# 2019_FDP_SCHEMA.net
KiCad netlist of a schematic drawn in Altium Designer
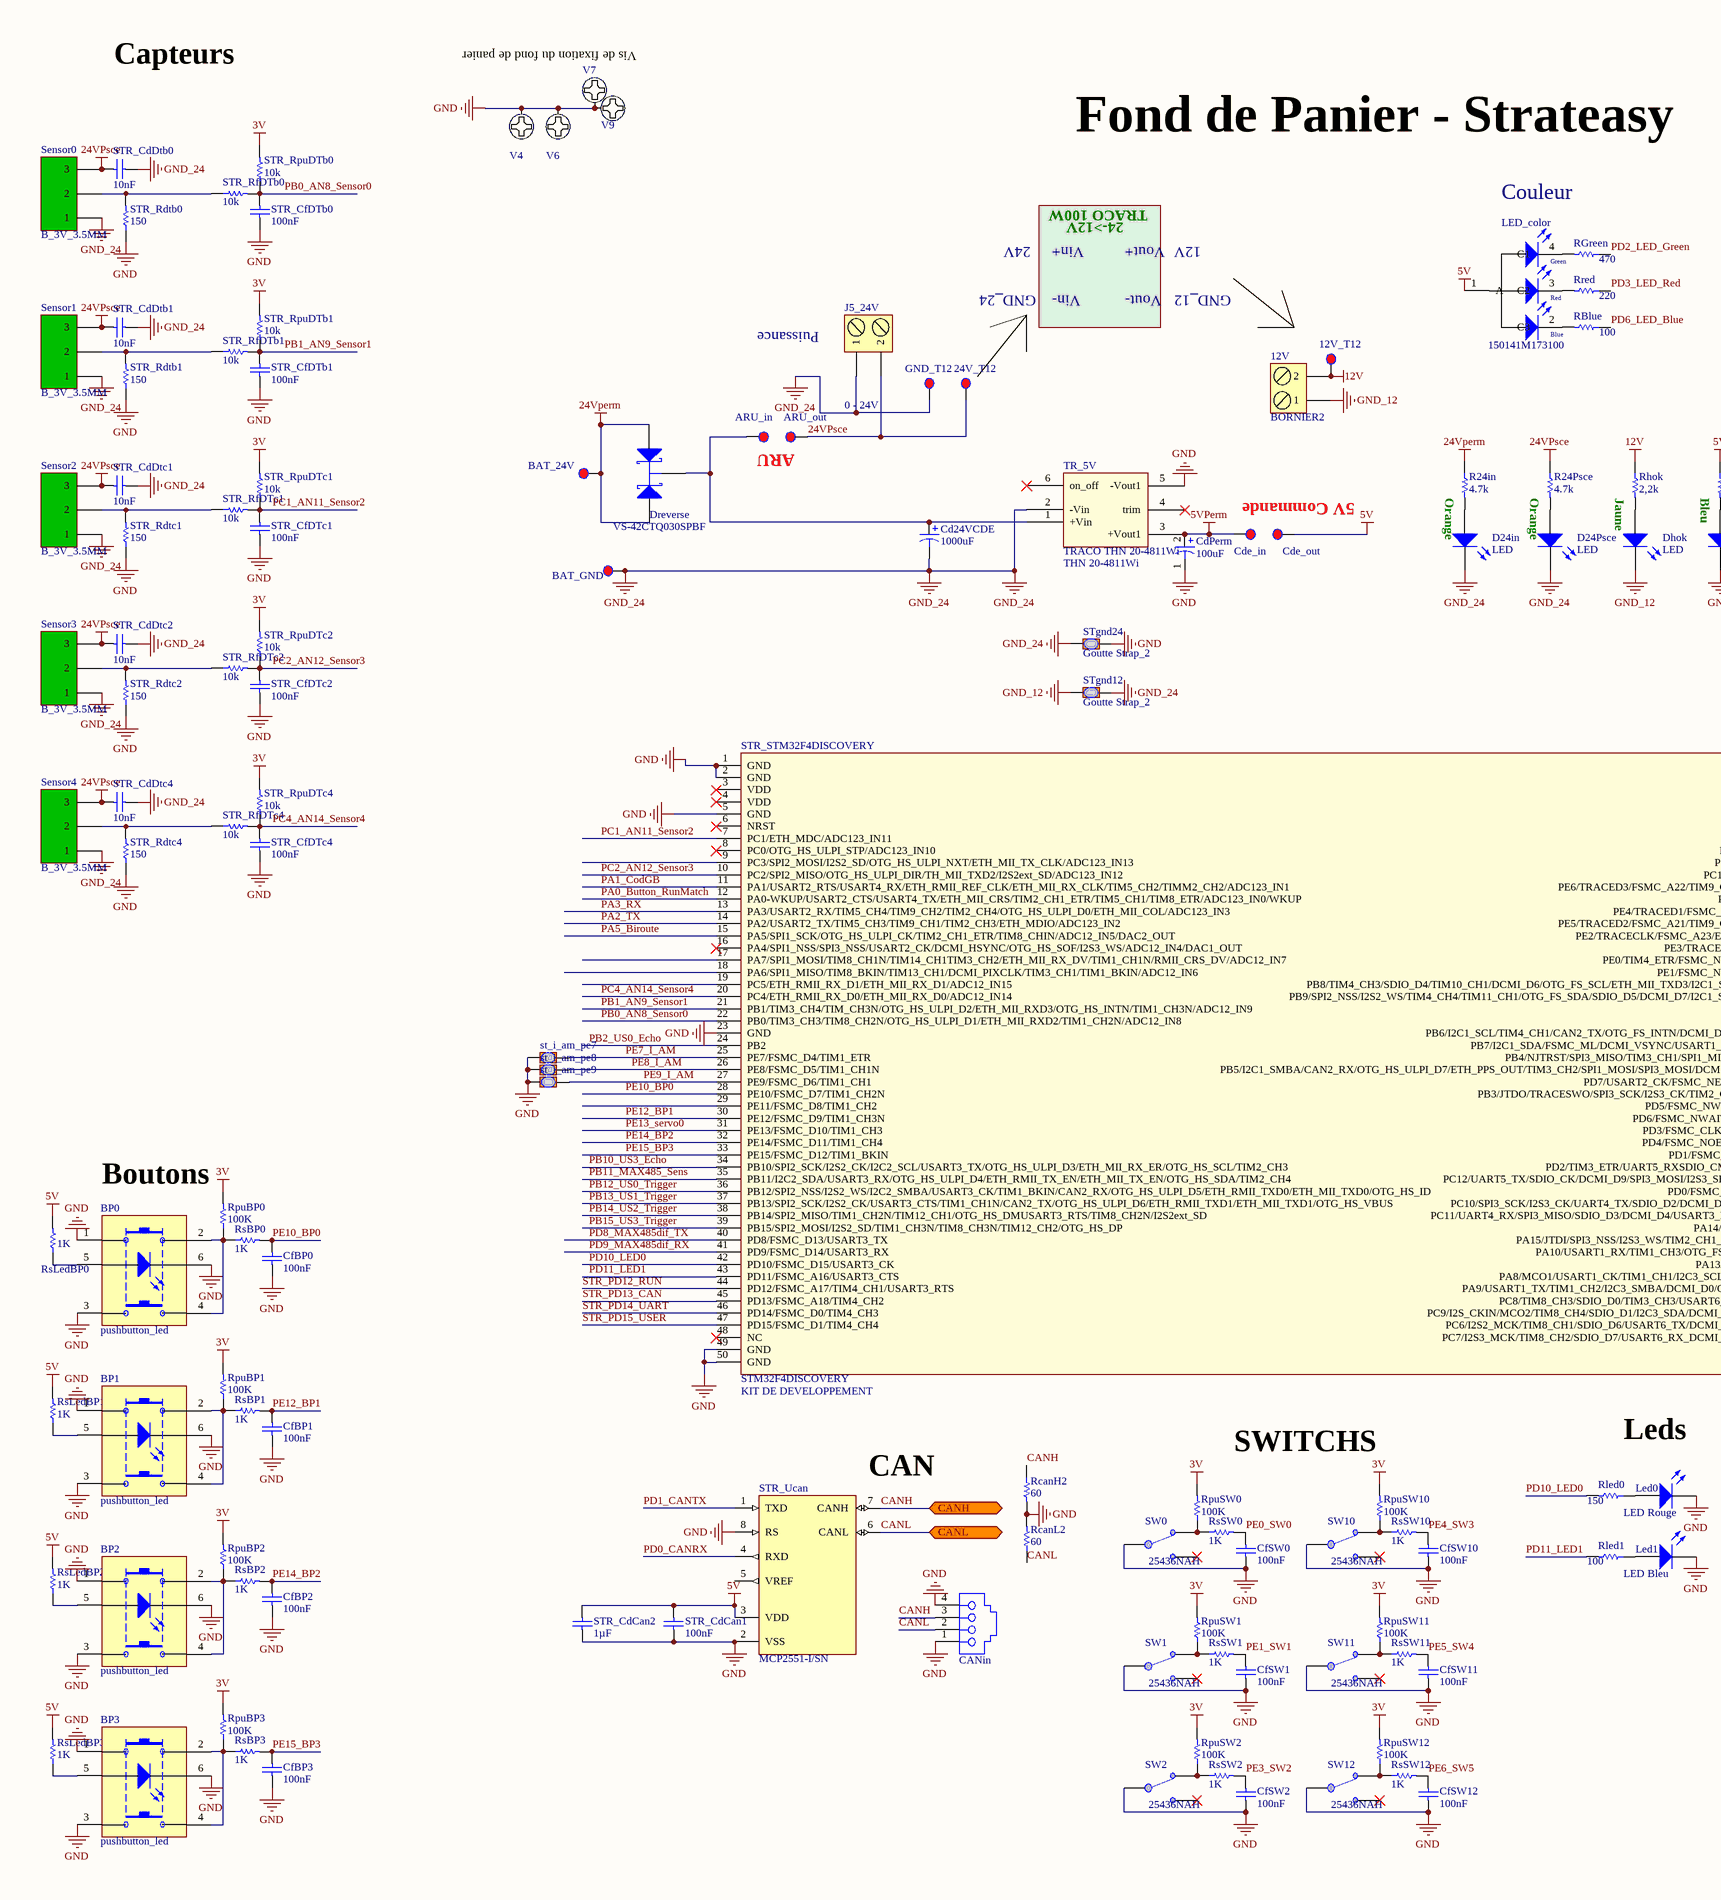
[diagram p0: 2019_FDP_SCHEMA.SchDoc, left]
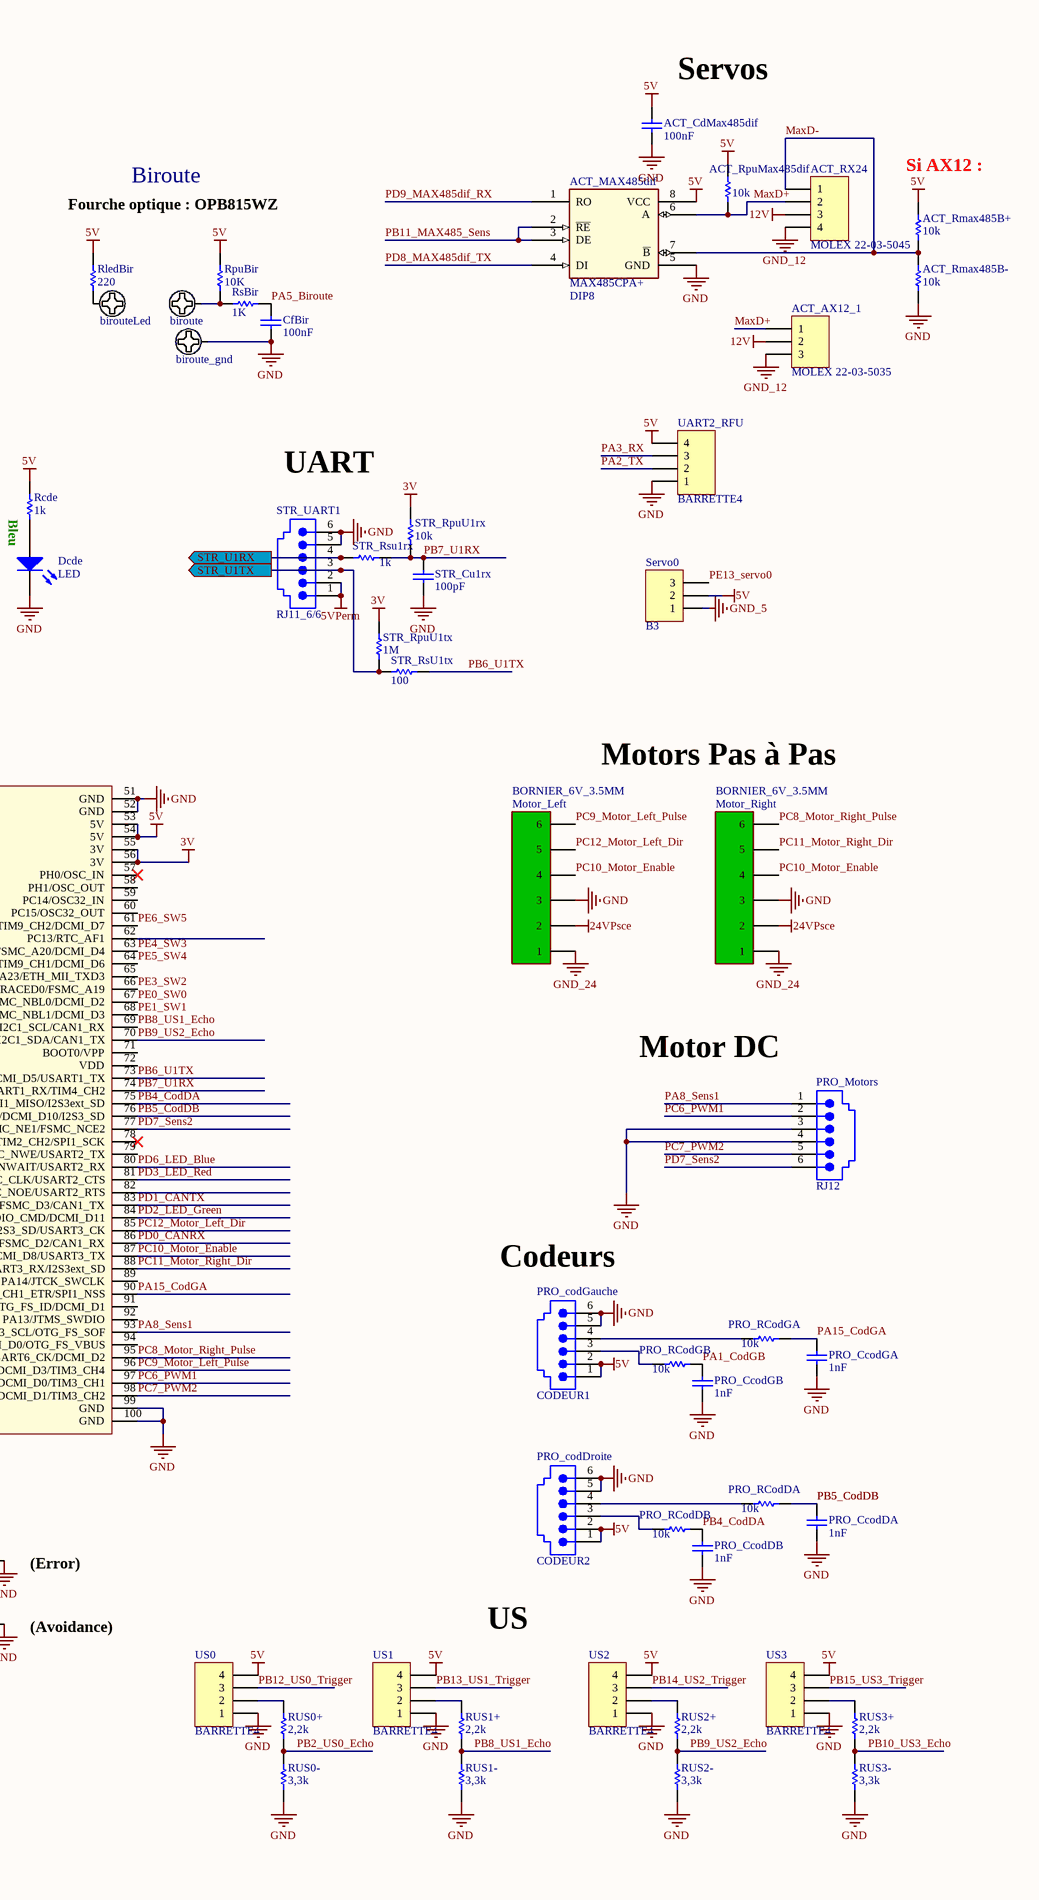
[diagram p1: 2019_FDP_SCHEMA.SchDoc, right]

(export (version "E")
  (design (tool "Eeschema 10.0.6"))
  (components
    (comp (ref "12V")
      (value "BORNIER2")
      (footprint "BORNIER_2V_5.08MM")
      (description "Terminal blocks, 2 pins, pitch=5mm")
      (libsource (lib "Connecteur") (part "BORNIER2"))
    )
    (comp (ref "12V_T12")
      (value "Name")
      (footprint "Point Test_D3_P1.6mm")
      (description "Point test")
      (fields (field (name "PUBLISHER") "Damien GUITTON"))
      (libsource (lib "DG_Connecteur") (part "Point Test"))
    )
    (comp (ref "24V_T12")
      (value "Name")
      (footprint "Point Test_D3_P1.6mm")
      (description "Point test")
      (fields (field (name "PUBLISHER") "Damien GUITTON"))
      (libsource (lib "DG_Connecteur") (part "Point Test"))
    )
    (comp (ref "ACT_AX12_1")
      (value "MOLEX 22-03-5035")
      (footprint "MOLEX3_2.5MM")
      (description "Header, 3-Pin")
      (fields (field (name "PUBLISHER") "Altium Limited"))
      (libsource (lib "Connecteur") (part "BARRETTE3"))
    )
    (comp (ref "ACT_CdMax485dif")
      (value "100nF")
      (footprint "C0805_N")
      (description "Capacitor")
      (fields (field (name "PUBLISHER") "Altium Limited"))
      (libsource (lib "_ROBOT") (part "Condensateur"))
    )
    (comp (ref "ACT_MAX485dif")
      (value "MAX485CPA+_DIP8")
      (footprint "SO8_N")
      (description "EMETTEUR/RECEPTEUR FAIBLE PUISSANCE DE LIAISONS RS422/RS485 - DIP8")
      (fields (field (name "TYPE") "MAX485CPA+") (field (name "PACKAGE") "DIP8"))
      (libsource (lib "circuits integres") (part "MAX485CPA+_DIP8"))
    )
    (comp (ref "ACT_Rmax485B+")
      (value "10k")
      (footprint "R1206_N")
      (description "Resistor")
      (fields (field (name "PUBLISHER") "Altium Limited"))
      (libsource (lib "_ROBOT") (part "Resistor"))
    )
    (comp (ref "ACT_Rmax485B-")
      (value "10k")
      (footprint "R1206_N")
      (description "Resistor")
      (fields (field (name "PUBLISHER") "Altium Limited"))
      (libsource (lib "_ROBOT") (part "Resistor"))
    )
    (comp (ref "ACT_RpuMax485dif")
      (value "10k")
      (footprint "R1206_N")
      (description "Resistor")
      (fields (field (name "PUBLISHER") "Altium Limited"))
      (libsource (lib "_ROBOT") (part "Resistor"))
    )
    (comp (ref "ACT_RX24")
      (value "MOLEX 22-03-5045")
      (footprint "MOLEX4_2.5MM")
      (description "Header, 4-Pin")
      (fields (field (name "PUBLISHER") "Altium Limited"))
      (libsource (lib "") (part "BARRETTE4_1"))
    )
    (comp (ref "ARU_in")
      (value "Name")
      (footprint "Point Test_D3_P1.6mm")
      (description "Point test")
      (fields (field (name "PUBLISHER") "Damien GUITTON"))
      (libsource (lib "DG_Connecteur") (part "Point Test"))
    )
    (comp (ref "ARU_out")
      (value "Name")
      (footprint "Point Test_D3_P1.6mm")
      (description "Point test")
      (fields (field (name "PUBLISHER") "Damien GUITTON"))
      (libsource (lib "DG_Connecteur") (part "Point Test"))
    )
    (comp (ref "BAT_24V")
      (value "Name")
      (footprint "Point Test_D3_P1.6mm")
      (description "Point test")
      (fields (field (name "PUBLISHER") "Damien GUITTON"))
      (libsource (lib "DG_Connecteur") (part "Point Test"))
    )
    (comp (ref "BAT_GND")
      (value "Name")
      (footprint "Point Test_D3_P1.6mm")
      (description "Point test")
      (fields (field (name "PUBLISHER") "Damien GUITTON"))
      (libsource (lib "DG_Connecteur") (part "Point Test"))
    )
    (comp (ref "biroute")
      (value "Pad_M3")
      (footprint "PAD_CMS_5.08x2.54")
      (description "Vis M3 X 6mm _TORX_Tête 6mm")
      (fields (field (name "PUBLISHER") "Damien Guitton"))
      (libsource (lib "_ROBOT") (part "Vis M3 X 6mm _TORX_Tête 6mm"))
    )
    (comp (ref "birouteLed")
      (value "Pad_M3")
      (footprint "PAD_CMS_5.08x2.54")
      (description "Vis M3 X 6mm _TORX_Tête 6mm")
      (fields (field (name "PUBLISHER") "Damien Guitton"))
      (libsource (lib "_ROBOT") (part "Vis M3 X 6mm _TORX_Tête 6mm"))
    )
    (comp (ref "biroute_gnd")
      (value "Pad_M3")
      (footprint "PAD_CMS_5.08x2.54")
      (description "Vis M3 X 6mm _TORX_Tête 6mm")
      (fields (field (name "PUBLISHER") "Damien Guitton"))
      (libsource (lib "_ROBOT") (part "Vis M3 X 6mm _TORX_Tête 6mm"))
    )
    (comp (ref "BP0")
      (value "pushbutton_led")
      (footprint "PUSHBUTTON_LED")
      (libsource (lib "_ROBOT") (part "pushbutton_led"))
    )
    (comp (ref "BP1")
      (value "pushbutton_led")
      (footprint "PUSHBUTTON_LED")
      (libsource (lib "_ROBOT") (part "pushbutton_led"))
    )
    (comp (ref "BP2")
      (value "pushbutton_led")
      (footprint "PUSHBUTTON_LED")
      (libsource (lib "_ROBOT") (part "pushbutton_led"))
    )
    (comp (ref "BP3")
      (value "pushbutton_led")
      (footprint "PUSHBUTTON_LED")
      (libsource (lib "_ROBOT") (part "pushbutton_led"))
    )
    (comp (ref "CANin")
      (value "634104149621")
      (footprint "634104149621")
      (description "Modular Jack SMT Vertical Plastic 4P4C Top Entry WR-MJ")
      (fields (field (name "PUBLISHER") "Wurth Elektronik"))
      (libsource (lib "ALTIUM-MJ_VERTICAL_PLASTIC") (part "634104149621"))
    )
    (comp (ref "Cd24VCDE")
      (value "1000uF")
      (footprint "RESISTANCE_5W")
      (description "Polarized Capacitor")
      (libsource (lib "_ROBOT") (part "Condensateur Polarise Traversant"))
    )
    (comp (ref "Cde_in")
      (value "Name")
      (footprint "Point Test_D3_P1.6mm")
      (description "Point test")
      (fields (field (name "PUBLISHER") "Damien GUITTON"))
      (libsource (lib "DG_Connecteur") (part "Point Test"))
    )
    (comp (ref "Cde_out")
      (value "Name")
      (footprint "Point Test_D3_P1.6mm")
      (description "Point test")
      (fields (field (name "PUBLISHER") "Damien GUITTON"))
      (libsource (lib "DG_Connecteur") (part "Point Test"))
    )
    (comp (ref "CdPerm")
      (value "100uF")
      (footprint "CONDENSATEUR_POLARISE_ELECTROLYTIQUE_RADIAL_5.08/8.9")
      (description "Polarized Capacitor")
      (libsource (lib "") (part "Condensateur Polarise Traversant_1"))
    )
    (comp (ref "CfBir")
      (value "100nF")
      (footprint "C0805_N")
      (description "Capacitor")
      (fields (field (name "PUBLISHER") "Altium Limited"))
      (libsource (lib "_ROBOT") (part "Condensateur"))
    )
    (comp (ref "CfBP0")
      (value "100nF")
      (footprint "C0805_N")
      (description "Capacitor")
      (fields (field (name "PUBLISHER") "Altium Limited"))
      (libsource (lib "_ROBOT") (part "Condensateur"))
    )
    (comp (ref "CfBP1")
      (value "100nF")
      (footprint "C0805_N")
      (description "Capacitor")
      (fields (field (name "PUBLISHER") "Altium Limited"))
      (libsource (lib "_ROBOT") (part "Condensateur"))
    )
    (comp (ref "CfBP2")
      (value "100nF")
      (footprint "C0805_N")
      (description "Capacitor")
      (fields (field (name "PUBLISHER") "Altium Limited"))
      (libsource (lib "_ROBOT") (part "Condensateur"))
    )
    (comp (ref "CfBP3")
      (value "100nF")
      (footprint "C0805_N")
      (description "Capacitor")
      (fields (field (name "PUBLISHER") "Altium Limited"))
      (libsource (lib "_ROBOT") (part "Condensateur"))
    )
    (comp (ref "CfSW0")
      (value "100nF")
      (footprint "C0805_N")
      (description "Capacitor")
      (fields (field (name "PUBLISHER") "Altium Limited"))
      (libsource (lib "_ROBOT") (part "Condensateur"))
    )
    (comp (ref "CfSW1")
      (value "100nF")
      (footprint "C0805_N")
      (description "Capacitor")
      (fields (field (name "PUBLISHER") "Altium Limited"))
      (libsource (lib "_ROBOT") (part "Condensateur"))
    )
    (comp (ref "CfSW2")
      (value "100nF")
      (footprint "C0805_N")
      (description "Capacitor")
      (fields (field (name "PUBLISHER") "Altium Limited"))
      (libsource (lib "_ROBOT") (part "Condensateur"))
    )
    (comp (ref "CfSW10")
      (value "100nF")
      (footprint "C0805_N")
      (description "Capacitor")
      (fields (field (name "PUBLISHER") "Altium Limited"))
      (libsource (lib "_ROBOT") (part "Condensateur"))
    )
    (comp (ref "CfSW11")
      (value "100nF")
      (footprint "C0805_N")
      (description "Capacitor")
      (fields (field (name "PUBLISHER") "Altium Limited"))
      (libsource (lib "_ROBOT") (part "Condensateur"))
    )
    (comp (ref "CfSW12")
      (value "100nF")
      (footprint "C0805_N")
      (description "Capacitor")
      (fields (field (name "PUBLISHER") "Altium Limited"))
      (libsource (lib "_ROBOT") (part "Condensateur"))
    )
    (comp (ref "D24in")
      (value "LED")
      (footprint "LED_0805")
      (description "Typical LED")
      (fields (field (name "PUBLISHER") "Altium Limited"))
      (libsource (lib "_ROBOT") (part "LED"))
    )
    (comp (ref "D24Psce")
      (value "LED")
      (footprint "LED_0805")
      (description "Typical LED")
      (fields (field (name "PUBLISHER") "Altium Limited"))
      (libsource (lib "_ROBOT") (part "LED"))
    )
    (comp (ref "Dcde")
      (value "LED")
      (footprint "LED_0805")
      (description "Typical LED")
      (fields (field (name "PUBLISHER") "Altium Limited"))
      (libsource (lib "_ROBOT") (part "LED"))
    )
    (comp (ref "Dhok")
      (value "LED")
      (footprint "LED_0805")
      (description "Typical LED")
      (fields (field (name "PUBLISHER") "Altium Limited"))
      (libsource (lib "_ROBOT") (part "LED"))
    )
    (comp (ref "Dreverse")
      (value "VS-42CTQ030SPBF")
      (footprint "D2Pak (123)")
      (description "DIODE SCHOTTKY DOUBLE")
      (fields (field (name "MANUFACTURER PART NUMBER") "BAT54C") (field (name "MANUFACTURER") "ZETEX"))
      (libsource (lib "_ROBOT") (part "Diode Shottky double BAT54C"))
    )
    (comp (ref "GND_T12")
      (value "Name")
      (footprint "Point Test_D3_P1.6mm")
      (description "Point test")
      (fields (field (name "PUBLISHER") "Damien GUITTON"))
      (libsource (lib "DG_Connecteur") (part "Point Test"))
    )
    (comp (ref "J5_24V")
      (value "0 - 24V")
      (footprint "BORNIER2_FEM_COUDE")
      (description "Terminal blocks, 2 pins, pitch=5mm")
      (libsource (lib "miniprojet") (part "BORNIER2"))
    )
    (comp (ref "Led0")
      (value "LED Rouge")
      (footprint "LED_0805")
      (description "Typical LED")
      (fields (field (name "PUBLISHER") "Altium Limited"))
      (libsource (lib "DG_LED") (part "LED"))
    )
    (comp (ref "Led1")
      (value "LED Bleu")
      (footprint "LED_0805")
      (description "Typical LED")
      (fields (field (name "PUBLISHER") "Altium Limited"))
      (libsource (lib "DG_LED") (part "LED"))
    )
    (comp (ref "LED_color")
      (value "150141M173100")
      (footprint "3528")
      (description "SMD Full-Color Top LED, WL-SFTW, Red & Green & Blue")
      (fields
        (field (name "MANUFACTURER") "Würth Elektronik eiSos GmbH")
        (field (name "CREATED BY") "Christin Otto")
      )
      (libsource (lib "WL-SFTW") (part "WL-SFTW 3528 150141M173100"))
    )
    (comp (ref "Motor_Left")
      (value "BORNIER_6V_3.5MM")
      (footprint "BORNIER_6V_3.5MM")
      (libsource (lib "Connecteur") (part "BORNIER_6V_3.5MM"))
    )
    (comp (ref "Motor_Right")
      (value "BORNIER_6V_3.5MM")
      (footprint "BORNIER_6V_3.5MM")
      (libsource (lib "Connecteur") (part "BORNIER_6V_3.5MM"))
    )
    (comp (ref "PRO_CcodDA")
      (value "1nF")
      (footprint "C0805_N")
      (description "Capacitor")
      (fields (field (name "PUBLISHER") "Altium Limited"))
      (libsource (lib "_ROBOT") (part "Condensateur"))
    )
    (comp (ref "PRO_CcodDB")
      (value "1nF")
      (footprint "C0805_N")
      (description "Capacitor")
      (fields (field (name "PUBLISHER") "Altium Limited"))
      (libsource (lib "_ROBOT") (part "Condensateur"))
    )
    (comp (ref "PRO_CcodGA")
      (value "1nF")
      (footprint "C0805_N")
      (description "Capacitor")
      (fields (field (name "PUBLISHER") "Altium Limited"))
      (libsource (lib "_ROBOT") (part "Condensateur"))
    )
    (comp (ref "PRO_CcodGB")
      (value "1nF")
      (footprint "C0805_N")
      (description "Capacitor")
      (fields (field (name "PUBLISHER") "Altium Limited"))
      (libsource (lib "_ROBOT") (part "Condensateur"))
    )
    (comp (ref "PRO_codDroite")
      (value "CODEUR2")
      (footprint "RJ11_6/6 - droit")
      (description "Right Angle, Standard Profile, Offset Latch DECconnect, Flangeless PCB Jack")
      (fields (field (name "PUBLISHER") "Altium Limited"))
      (libsource (lib "miniprojet") (part "RJ11_6/6"))
    )
    (comp (ref "PRO_codGauche")
      (value "CODEUR1")
      (footprint "RJ11_6/6 - droit")
      (description "Right Angle, Standard Profile, Offset Latch DECconnect, Flangeless PCB Jack")
      (fields (field (name "PUBLISHER") "Altium Limited"))
      (libsource (lib "miniprojet") (part "RJ11_6/6"))
    )
    (comp (ref "PRO_Motors")
      (value "RJ12")
      (footprint "RJ11_6/6 - droit")
      (description "Right Angle, Standard Profile, Offset Latch DECconnect, Flangeless PCB Jack")
      (fields (field (name "PUBLISHER") "Altium Limited"))
      (libsource (lib "Connecteur") (part "RJ11_6/6"))
    )
    (comp (ref "PRO_RCodDA")
      (value "10k")
      (footprint "R1206_N")
      (description "Resistor")
      (fields (field (name "PUBLISHER") "Altium Limited"))
      (libsource (lib "_ROBOT") (part "Resistor"))
    )
    (comp (ref "PRO_RCodDB")
      (value "10k")
      (footprint "R1206_N")
      (description "Resistor")
      (fields (field (name "PUBLISHER") "Altium Limited"))
      (libsource (lib "_ROBOT") (part "Resistor"))
    )
    (comp (ref "PRO_RCodGA")
      (value "10k")
      (footprint "R1206_N")
      (description "Resistor")
      (fields (field (name "PUBLISHER") "Altium Limited"))
      (libsource (lib "_ROBOT") (part "Resistor"))
    )
    (comp (ref "PRO_RCodGB")
      (value "10k")
      (footprint "R1206_N")
      (description "Resistor")
      (fields (field (name "PUBLISHER") "Altium Limited"))
      (libsource (lib "_ROBOT") (part "Resistor"))
    )
    (comp (ref "R24in")
      (value "4.7k")
      (footprint "R1206_N")
      (description "Resistor")
      (fields (field (name "PUBLISHER") "Altium Limited"))
      (libsource (lib "_ROBOT") (part "Resistor"))
    )
    (comp (ref "R24Psce")
      (value "4.7k")
      (footprint "R1206_N")
      (description "Resistor")
      (fields (field (name "PUBLISHER") "Altium Limited"))
      (libsource (lib "_ROBOT") (part "Resistor"))
    )
    (comp (ref "RBlue")
      (value "100")
      (footprint "R1206_N")
      (description "Resistor")
      (fields (field (name "PUBLISHER") "Altium Limited"))
      (libsource (lib "_ROBOT") (part "Resistor"))
    )
    (comp (ref "RcanH2")
      (value "60")
      (footprint "R1206_N")
      (description "Resistor")
      (fields (field (name "PUBLISHER") "Altium Limited"))
      (libsource (lib "_ROBOT") (part "Resistor"))
    )
    (comp (ref "RcanL2")
      (value "60")
      (footprint "R1206_N")
      (description "Resistor")
      (fields (field (name "PUBLISHER") "Altium Limited"))
      (libsource (lib "_ROBOT") (part "Resistor"))
    )
    (comp (ref "Rcde")
      (value "1k")
      (footprint "R1206_N")
      (description "Resistor")
      (fields (field (name "PUBLISHER") "Altium Limited"))
      (libsource (lib "_ROBOT") (part "Resistor"))
    )
    (comp (ref "RGreen")
      (value "470")
      (footprint "R1206_N")
      (description "Resistor")
      (fields (field (name "PUBLISHER") "Altium Limited"))
      (libsource (lib "_ROBOT") (part "Resistor"))
    )
    (comp (ref "Rhok")
      (value "2,2k")
      (footprint "R1206_N")
      (description "Resistor")
      (fields (field (name "PUBLISHER") "Altium Limited"))
      (libsource (lib "_ROBOT") (part "Resistor"))
    )
    (comp (ref "Rled0")
      (value "150")
      (footprint "R1206_N")
      (description "Resistor")
      (fields (field (name "PUBLISHER") "Altium Limited"))
      (libsource (lib "_ROBOT") (part "Resistor"))
    )
    (comp (ref "Rled1")
      (value "100")
      (footprint "R1206_N")
      (description "Resistor")
      (fields (field (name "PUBLISHER") "Altium Limited"))
      (libsource (lib "_ROBOT") (part "Resistor"))
    )
    (comp (ref "RledBir")
      (value "220")
      (footprint "R1206_N")
      (description "Resistor")
      (fields (field (name "PUBLISHER") "Altium Limited"))
      (libsource (lib "_ROBOT") (part "Resistor"))
    )
    (comp (ref "RpuBir")
      (value "10K")
      (footprint "R1206_N")
      (description "Resistor")
      (fields (field (name "PUBLISHER") "Altium Limited"))
      (libsource (lib "_ROBOT") (part "Resistor"))
    )
    (comp (ref "RpuBP0")
      (value "100K")
      (footprint "R1206_N")
      (description "Resistor")
      (fields (field (name "PUBLISHER") "Altium Limited"))
      (libsource (lib "_ROBOT") (part "Resistor"))
    )
    (comp (ref "RpuBP1")
      (value "100K")
      (footprint "R1206_N")
      (description "Resistor")
      (fields (field (name "PUBLISHER") "Altium Limited"))
      (libsource (lib "_ROBOT") (part "Resistor"))
    )
    (comp (ref "RpuBP2")
      (value "100K")
      (footprint "R1206_N")
      (description "Resistor")
      (fields (field (name "PUBLISHER") "Altium Limited"))
      (libsource (lib "_ROBOT") (part "Resistor"))
    )
    (comp (ref "RpuBP3")
      (value "100K")
      (footprint "R1206_N")
      (description "Resistor")
      (fields (field (name "PUBLISHER") "Altium Limited"))
      (libsource (lib "_ROBOT") (part "Resistor"))
    )
    (comp (ref "RpuSW0")
      (value "100K")
      (footprint "R1206_N")
      (description "Resistor")
      (fields (field (name "PUBLISHER") "Altium Limited"))
      (libsource (lib "_ROBOT") (part "Resistor"))
    )
    (comp (ref "RpuSW1")
      (value "100K")
      (footprint "R1206_N")
      (description "Resistor")
      (fields (field (name "PUBLISHER") "Altium Limited"))
      (libsource (lib "_ROBOT") (part "Resistor"))
    )
    (comp (ref "RpuSW2")
      (value "100K")
      (footprint "R1206_N")
      (description "Resistor")
      (fields (field (name "PUBLISHER") "Altium Limited"))
      (libsource (lib "_ROBOT") (part "Resistor"))
    )
    (comp (ref "RpuSW10")
      (value "100K")
      (footprint "R1206_N")
      (description "Resistor")
      (fields (field (name "PUBLISHER") "Altium Limited"))
      (libsource (lib "_ROBOT") (part "Resistor"))
    )
    (comp (ref "RpuSW11")
      (value "100K")
      (footprint "R1206_N")
      (description "Resistor")
      (fields (field (name "PUBLISHER") "Altium Limited"))
      (libsource (lib "_ROBOT") (part "Resistor"))
    )
    (comp (ref "RpuSW12")
      (value "100K")
      (footprint "R1206_N")
      (description "Resistor")
      (fields (field (name "PUBLISHER") "Altium Limited"))
      (libsource (lib "_ROBOT") (part "Resistor"))
    )
    (comp (ref "Rred")
      (value "220")
      (footprint "R1206_N")
      (description "Resistor")
      (fields (field (name "PUBLISHER") "Altium Limited"))
      (libsource (lib "_ROBOT") (part "Resistor"))
    )
    (comp (ref "RsBir")
      (value "1K")
      (footprint "R1206_N")
      (description "Resistor")
      (fields (field (name "PUBLISHER") "Altium Limited"))
      (libsource (lib "_ROBOT") (part "Resistor"))
    )
    (comp (ref "RsBP0")
      (value "1K")
      (footprint "R1206_N")
      (description "Resistor")
      (fields (field (name "PUBLISHER") "Altium Limited"))
      (libsource (lib "_ROBOT") (part "Resistor"))
    )
    (comp (ref "RsBP1")
      (value "1K")
      (footprint "R1206_N")
      (description "Resistor")
      (fields (field (name "PUBLISHER") "Altium Limited"))
      (libsource (lib "_ROBOT") (part "Resistor"))
    )
    (comp (ref "RsBP2")
      (value "1K")
      (footprint "R1206_N")
      (description "Resistor")
      (fields (field (name "PUBLISHER") "Altium Limited"))
      (libsource (lib "_ROBOT") (part "Resistor"))
    )
    (comp (ref "RsBP3")
      (value "1K")
      (footprint "R1206_N")
      (description "Resistor")
      (fields (field (name "PUBLISHER") "Altium Limited"))
      (libsource (lib "_ROBOT") (part "Resistor"))
    )
    (comp (ref "RsLedBP0")
      (value "1K")
      (footprint "R1206_N")
      (description "Resistor")
      (fields (field (name "PUBLISHER") "Altium Limited"))
      (libsource (lib "_ROBOT") (part "Resistor"))
    )
    (comp (ref "RsLedBP1")
      (value "1K")
      (footprint "R1206_N")
      (description "Resistor")
      (fields (field (name "PUBLISHER") "Altium Limited"))
      (libsource (lib "_ROBOT") (part "Resistor"))
    )
    (comp (ref "RsLedBP2")
      (value "1K")
      (footprint "R1206_N")
      (description "Resistor")
      (fields (field (name "PUBLISHER") "Altium Limited"))
      (libsource (lib "_ROBOT") (part "Resistor"))
    )
    (comp (ref "RsLedBP3")
      (value "1K")
      (footprint "R1206_N")
      (description "Resistor")
      (fields (field (name "PUBLISHER") "Altium Limited"))
      (libsource (lib "_ROBOT") (part "Resistor"))
    )
    (comp (ref "RsSW0")
      (value "1K")
      (footprint "R1206_N")
      (description "Resistor")
      (fields (field (name "PUBLISHER") "Altium Limited"))
      (libsource (lib "_ROBOT") (part "Resistor"))
    )
    (comp (ref "RsSW1")
      (value "1K")
      (footprint "R1206_N")
      (description "Resistor")
      (fields (field (name "PUBLISHER") "Altium Limited"))
      (libsource (lib "_ROBOT") (part "Resistor"))
    )
    (comp (ref "RsSW2")
      (value "1K")
      (footprint "R1206_N")
      (description "Resistor")
      (fields (field (name "PUBLISHER") "Altium Limited"))
      (libsource (lib "_ROBOT") (part "Resistor"))
    )
    (comp (ref "RsSW10")
      (value "1K")
      (footprint "R1206_N")
      (description "Resistor")
      (fields (field (name "PUBLISHER") "Altium Limited"))
      (libsource (lib "_ROBOT") (part "Resistor"))
    )
    (comp (ref "RsSW11")
      (value "1K")
      (footprint "R1206_N")
      (description "Resistor")
      (fields (field (name "PUBLISHER") "Altium Limited"))
      (libsource (lib "_ROBOT") (part "Resistor"))
    )
    (comp (ref "RsSW12")
      (value "1K")
      (footprint "R1206_N")
      (description "Resistor")
      (fields (field (name "PUBLISHER") "Altium Limited"))
      (libsource (lib "_ROBOT") (part "Resistor"))
    )
    (comp (ref "RUS0+")
      (value "2,2k")
      (footprint "R1206_N")
      (description "Resistor")
      (fields (field (name "PUBLISHER") "Altium Limited"))
      (libsource (lib "_ROBOT") (part "Resistor"))
    )
    (comp (ref "RUS0-")
      (value "3,3k")
      (footprint "R1206_N")
      (description "Resistor")
      (fields (field (name "PUBLISHER") "Altium Limited"))
      (libsource (lib "_ROBOT") (part "Resistor"))
    )
    (comp (ref "RUS1+")
      (value "2,2k")
      (footprint "R1206_N")
      (description "Resistor")
      (fields (field (name "PUBLISHER") "Altium Limited"))
      (libsource (lib "_ROBOT") (part "Resistor"))
    )
    (comp (ref "RUS1-")
      (value "3,3k")
      (footprint "R1206_N")
      (description "Resistor")
      (fields (field (name "PUBLISHER") "Altium Limited"))
      (libsource (lib "_ROBOT") (part "Resistor"))
    )
    (comp (ref "RUS2+")
      (value "2,2k")
      (footprint "R1206_N")
      (description "Resistor")
      (fields (field (name "PUBLISHER") "Altium Limited"))
      (libsource (lib "_ROBOT") (part "Resistor"))
    )
    (comp (ref "RUS2-")
      (value "3,3k")
      (footprint "R1206_N")
      (description "Resistor")
      (fields (field (name "PUBLISHER") "Altium Limited"))
      (libsource (lib "_ROBOT") (part "Resistor"))
    )
    (comp (ref "RUS3+")
      (value "2,2k")
      (footprint "R1206_N")
      (description "Resistor")
      (fields (field (name "PUBLISHER") "Altium Limited"))
      (libsource (lib "_ROBOT") (part "Resistor"))
    )
    (comp (ref "RUS3-")
      (value "3,3k")
      (footprint "R1206_N")
      (description "Resistor")
      (fields (field (name "PUBLISHER") "Altium Limited"))
      (libsource (lib "_ROBOT") (part "Resistor"))
    )
    (comp (ref "Sensor0")
      (value "B_3V_3.5MM")
      (footprint "BORNIER_3V_3.5MM")
      (libsource (lib "Connecteur") (part "BORNIER_3V_3.5MM"))
    )
    (comp (ref "Sensor1")
      (value "B_3V_3.5MM")
      (footprint "BORNIER_3V_3.5MM")
      (libsource (lib "Connecteur") (part "BORNIER_3V_3.5MM"))
    )
    (comp (ref "Sensor2")
      (value "B_3V_3.5MM")
      (footprint "BORNIER_3V_3.5MM")
      (libsource (lib "Connecteur") (part "BORNIER_3V_3.5MM"))
    )
    (comp (ref "Sensor3")
      (value "B_3V_3.5MM")
      (footprint "BORNIER_3V_3.5MM")
      (libsource (lib "Connecteur") (part "BORNIER_3V_3.5MM"))
    )
    (comp (ref "Sensor4")
      (value "B_3V_3.5MM")
      (footprint "BORNIER_3V_3.5MM")
      (libsource (lib "Connecteur") (part "BORNIER_3V_3.5MM"))
    )
    (comp (ref "Servo0")
      (value "B3")
      (footprint "HE14_3")
      (description "Header, 3-Pin")
      (fields (field (name "PUBLISHER") "Altium Limited"))
      (libsource (lib "") (part "BARRETTE3_1"))
    )
    (comp (ref "STgnd12")
      (value "Goutte Strap_2")
      (footprint "Goutte Strap_2 Pads_Clearance 0.254mm")
      (fields (field (name "PUBLISHER") "Damien Guitton"))
      (libsource (lib "DG_Connecteur") (part "Goutte Strap_2"))
    )
    (comp (ref "STgnd24")
      (value "Goutte Strap_2")
      (footprint "Goutte Strap_2 Pads_Clearance 0.254mm")
      (fields (field (name "PUBLISHER") "Damien Guitton"))
      (libsource (lib "DG_Connecteur") (part "Goutte Strap_2"))
    )
    (comp (ref "STR_CdCan1")
      (value "100nF")
      (footprint "C0805_N")
      (description "Capacitor")
      (fields (field (name "PUBLISHER") "Altium Limited"))
      (libsource (lib "_ROBOT") (part "Condensateur"))
    )
    (comp (ref "STR_CdCan2")
      (value "1µF")
      (footprint "C0805_N")
      (description "Capacitor")
      (fields (field (name "PUBLISHER") "Altium Limited"))
      (libsource (lib "_ROBOT") (part "Condensateur"))
    )
    (comp (ref "STR_CdDtb0")
      (value "10nF")
      (footprint "C0805_N")
      (description "Capacitor")
      (fields (field (name "PUBLISHER") "Altium Limited"))
      (libsource (lib "_ROBOT") (part "Condensateur"))
    )
    (comp (ref "STR_CdDtb1")
      (value "10nF")
      (footprint "C0805_N")
      (description "Capacitor")
      (fields (field (name "PUBLISHER") "Altium Limited"))
      (libsource (lib "_ROBOT") (part "Condensateur"))
    )
    (comp (ref "STR_CdDtc1")
      (value "10nF")
      (footprint "C0805_N")
      (description "Capacitor")
      (fields (field (name "PUBLISHER") "Altium Limited"))
      (libsource (lib "_ROBOT") (part "Condensateur"))
    )
    (comp (ref "STR_CdDtc2")
      (value "10nF")
      (footprint "C0805_N")
      (description "Capacitor")
      (fields (field (name "PUBLISHER") "Altium Limited"))
      (libsource (lib "_ROBOT") (part "Condensateur"))
    )
    (comp (ref "STR_CdDtc4")
      (value "10nF")
      (footprint "C0805_N")
      (description "Capacitor")
      (fields (field (name "PUBLISHER") "Altium Limited"))
      (libsource (lib "_ROBOT") (part "Condensateur"))
    )
    (comp (ref "STR_CfDTb0")
      (value "100nF")
      (footprint "C0805_N")
      (description "Capacitor")
      (fields (field (name "PUBLISHER") "Altium Limited"))
      (libsource (lib "_ROBOT") (part "Condensateur"))
    )
    (comp (ref "STR_CfDTb1")
      (value "100nF")
      (footprint "C0805_N")
      (description "Capacitor")
      (fields (field (name "PUBLISHER") "Altium Limited"))
      (libsource (lib "_ROBOT") (part "Condensateur"))
    )
    (comp (ref "STR_CfDTc1")
      (value "100nF")
      (footprint "C0805_N")
      (description "Capacitor")
      (fields (field (name "PUBLISHER") "Altium Limited"))
      (libsource (lib "_ROBOT") (part "Condensateur"))
    )
    (comp (ref "STR_CfDTc2")
      (value "100nF")
      (footprint "C0805_N")
      (description "Capacitor")
      (fields (field (name "PUBLISHER") "Altium Limited"))
      (libsource (lib "_ROBOT") (part "Condensateur"))
    )
    (comp (ref "STR_CfDTc4")
      (value "100nF")
      (footprint "C0805_N")
      (description "Capacitor")
      (fields (field (name "PUBLISHER") "Altium Limited"))
      (libsource (lib "_ROBOT") (part "Condensateur"))
    )
    (comp (ref "STR_Cu1rx")
      (value "100pF")
      (footprint "C0805_N")
      (description "Capacitor")
      (fields (field (name "PUBLISHER") "Altium Limited"))
      (libsource (lib "_ROBOT") (part "Condensateur"))
    )
    (comp (ref "STR_Rdtb0")
      (value "150")
      (footprint "R1206_N")
      (description "Resistor")
      (fields (field (name "PUBLISHER") "Altium Limited"))
      (libsource (lib "_ROBOT") (part "Resistor"))
    )
    (comp (ref "STR_Rdtb1")
      (value "150")
      (footprint "R1206_N")
      (description "Resistor")
      (fields (field (name "PUBLISHER") "Altium Limited"))
      (libsource (lib "_ROBOT") (part "Resistor"))
    )
    (comp (ref "STR_Rdtc1")
      (value "150")
      (footprint "R1206_N")
      (description "Resistor")
      (fields (field (name "PUBLISHER") "Altium Limited"))
      (libsource (lib "_ROBOT") (part "Resistor"))
    )
    (comp (ref "STR_Rdtc2")
      (value "150")
      (footprint "R1206_N")
      (description "Resistor")
      (fields (field (name "PUBLISHER") "Altium Limited"))
      (libsource (lib "_ROBOT") (part "Resistor"))
    )
    (comp (ref "STR_Rdtc4")
      (value "150")
      (footprint "R1206_N")
      (description "Resistor")
      (fields (field (name "PUBLISHER") "Altium Limited"))
      (libsource (lib "_ROBOT") (part "Resistor"))
    )
    (comp (ref "STR_RfDTb0")
      (value "10k")
      (footprint "R1206_N")
      (description "Resistor")
      (fields (field (name "PUBLISHER") "Altium Limited"))
      (libsource (lib "_ROBOT") (part "Resistor"))
    )
    (comp (ref "STR_RfDTb1")
      (value "10k")
      (footprint "R1206_N")
      (description "Resistor")
      (fields (field (name "PUBLISHER") "Altium Limited"))
      (libsource (lib "_ROBOT") (part "Resistor"))
    )
    (comp (ref "STR_RfDTc1")
      (value "10k")
      (footprint "R1206_N")
      (description "Resistor")
      (fields (field (name "PUBLISHER") "Altium Limited"))
      (libsource (lib "_ROBOT") (part "Resistor"))
    )
    (comp (ref "STR_RfDTc2")
      (value "10k")
      (footprint "R1206_N")
      (description "Resistor")
      (fields (field (name "PUBLISHER") "Altium Limited"))
      (libsource (lib "_ROBOT") (part "Resistor"))
    )
    (comp (ref "STR_RfDTc4")
      (value "10k")
      (footprint "R1206_N")
      (description "Resistor")
      (fields (field (name "PUBLISHER") "Altium Limited"))
      (libsource (lib "_ROBOT") (part "Resistor"))
    )
    (comp (ref "STR_RpuDTb0")
      (value "10k")
      (footprint "R1206_N")
      (description "Resistor")
      (fields (field (name "PUBLISHER") "Altium Limited"))
      (libsource (lib "_ROBOT") (part "Resistor"))
    )
    (comp (ref "STR_RpuDTb1")
      (value "10k")
      (footprint "R1206_N")
      (description "Resistor")
      (fields (field (name "PUBLISHER") "Altium Limited"))
      (libsource (lib "_ROBOT") (part "Resistor"))
    )
    (comp (ref "STR_RpuDTc1")
      (value "10k")
      (footprint "R1206_N")
      (description "Resistor")
      (fields (field (name "PUBLISHER") "Altium Limited"))
      (libsource (lib "_ROBOT") (part "Resistor"))
    )
    (comp (ref "STR_RpuDTc2")
      (value "10k")
      (footprint "R1206_N")
      (description "Resistor")
      (fields (field (name "PUBLISHER") "Altium Limited"))
      (libsource (lib "_ROBOT") (part "Resistor"))
    )
    (comp (ref "STR_RpuDTc4")
      (value "10k")
      (footprint "R1206_N")
      (description "Resistor")
      (fields (field (name "PUBLISHER") "Altium Limited"))
      (libsource (lib "_ROBOT") (part "Resistor"))
    )
    (comp (ref "STR_RpuU1rx")
      (value "10k")
      (footprint "R1206_N")
      (description "Resistor")
      (fields (field (name "PUBLISHER") "Altium Limited"))
      (libsource (lib "_ROBOT") (part "Resistor"))
    )
    (comp (ref "STR_RpuU1tx")
      (value "1M")
      (footprint "R1206_N")
      (description "Resistor")
      (fields (field (name "PUBLISHER") "Altium Limited"))
      (libsource (lib "_ROBOT") (part "Resistor"))
    )
    (comp (ref "STR_Rsu1rx")
      (value "1k")
      (footprint "R1206_N")
      (description "Resistor")
      (fields (field (name "PUBLISHER") "Altium Limited"))
      (libsource (lib "_ROBOT") (part "Resistor"))
    )
    (comp (ref "STR_RsU1tx")
      (value "100")
      (footprint "R1206_N")
      (description "Resistor")
      (fields (field (name "PUBLISHER") "Altium Limited"))
      (libsource (lib "_ROBOT") (part "Resistor"))
    )
    (comp (ref "STR_STM32F4DISCOVERY")
      (value "STM32F4DISCOVERY")
      (footprint "STM32_F4DISCOVERY")
      (description "KIT DE DEVELOPPEMENT POUR MICROCONTROLEUR STM32F407VGT6")
      (fields (field (name "TYPE") "KIT DE DEVELOPPEMENT"))
      (libsource (lib "circuits integres") (part "STM32F4DISCOVERY"))
    )
    (comp (ref "STR_UART1")
      (value "RJ11_6/6")
      (footprint "RJ11_6/6 - droit")
      (description "Right Angle, Standard Profile, Offset Latch DECconnect, Flangeless PCB Jack")
      (fields (field (name "PUBLISHER") "Altium Limited"))
      (libsource (lib "Connecteur") (part "RJ11_6/6"))
    )
    (comp (ref "STR_Ucan")
      (value "MCP2551-I/SN")
      (footprint "SO8_N")
      (description "High-Speed CAN Transceiver, 8-Pin SOIC, Industrial Temperature")
      (fields (field (name "PUBLISHER") "Damien Guitton"))
      (libsource (lib "Circuit intégré") (part "MCP2551-I/SN"))
    )
    (comp (ref "st_i_am_pe7")
      (value "Goutte Strap_2")
      (footprint "Goutte Strap_2 Pads_Clearance 0.254mm")
      (fields (field (name "PUBLISHER") "Damien Guitton"))
      (libsource (lib "DG_Connecteur") (part "Goutte Strap_2"))
    )
    (comp (ref "st_i_am_pe8")
      (value "Goutte Strap_2")
      (footprint "Goutte Strap_2 Pads_Clearance 0.254mm")
      (fields (field (name "PUBLISHER") "Damien Guitton"))
      (libsource (lib "DG_Connecteur") (part "Goutte Strap_2"))
    )
    (comp (ref "st_i_am_pe9")
      (value "Goutte Strap_2")
      (footprint "Goutte Strap_2 Pads_Clearance 0.254mm")
      (fields (field (name "PUBLISHER") "Damien Guitton"))
      (libsource (lib "DG_Connecteur") (part "Goutte Strap_2"))
    )
    (comp (ref "SW0")
      (value "25436NAH")
      (footprint "SW_UNIPOL_DROIT - Ebay - SPDT - 11x6x5")
      (description "Switch unipolaire a levier")
      (libsource (lib "_ROBOT") (part "SW SPDT- APEM Série 523x"))
    )
    (comp (ref "SW1")
      (value "25436NAH")
      (footprint "SW_UNIPOL_DROIT - Ebay - SPDT - 11x6x5")
      (description "Switch unipolaire a levier")
      (libsource (lib "_ROBOT") (part "SW SPDT- APEM Série 523x"))
    )
    (comp (ref "SW2")
      (value "25436NAH")
      (footprint "SW_UNIPOL_DROIT - Ebay - SPDT - 11x6x5")
      (description "Switch unipolaire a levier")
      (libsource (lib "_ROBOT") (part "SW SPDT- APEM Série 523x"))
    )
    (comp (ref "SW10")
      (value "25436NAH")
      (footprint "SW_UNIPOL_DROIT - Ebay - SPDT - 11x6x5")
      (description "Switch unipolaire a levier")
      (libsource (lib "_ROBOT") (part "SW SPDT- APEM Série 523x"))
    )
    (comp (ref "SW11")
      (value "25436NAH")
      (footprint "SW_UNIPOL_DROIT - Ebay - SPDT - 11x6x5")
      (description "Switch unipolaire a levier")
      (libsource (lib "_ROBOT") (part "SW SPDT- APEM Série 523x"))
    )
    (comp (ref "SW12")
      (value "25436NAH")
      (footprint "SW_UNIPOL_DROIT - Ebay - SPDT - 11x6x5")
      (description "Switch unipolaire a levier")
      (libsource (lib "_ROBOT") (part "SW SPDT- APEM Série 523x"))
    )
    (comp (ref "TR_5V")
      (value "TRACO THN 20-4811Wi")
      (footprint "TRACO_THN20")
      (description "Traco 20W 24V to 5V*4A")
      (fields (field (name "REF") "THN 20-4811Wi"))
      (libsource (lib "_ROBOT") (part "TRACO THN 20-4811Wi"))
    )
    (comp (ref "UART2_RFU")
      (value "BARRETTE4")
      (footprint "HE14_4")
      (description "Header, 4-Pin")
      (fields (field (name "PUBLISHER") "Altium Limited"))
      (libsource (lib "") (part "BARRETTE4_2"))
    )
    (comp (ref "US0")
      (value "BARRETTE4")
      (footprint "HE14_4")
      (description "Header, 4-Pin")
      (fields (field (name "PUBLISHER") "Altium Limited"))
      (libsource (lib "Connecteur") (part "BARRETTE4"))
    )
    (comp (ref "US1")
      (value "BARRETTE4")
      (footprint "HE14_4")
      (description "Header, 4-Pin")
      (fields (field (name "PUBLISHER") "Altium Limited"))
      (libsource (lib "Connecteur") (part "BARRETTE4"))
    )
    (comp (ref "US2")
      (value "BARRETTE4")
      (footprint "HE14_4")
      (description "Header, 4-Pin")
      (fields (field (name "PUBLISHER") "Altium Limited"))
      (libsource (lib "Connecteur") (part "BARRETTE4"))
    )
    (comp (ref "US3")
      (value "BARRETTE4")
      (footprint "HE14_4")
      (description "Header, 4-Pin")
      (fields (field (name "PUBLISHER") "Altium Limited"))
      (libsource (lib "Connecteur") (part "BARRETTE4"))
    )
    (comp (ref "V4")
      (value "Pad_M3")
      (footprint "M3x6mm Torx")
      (description "Vis M3 X 6mm _TORX_Tête 6mm")
      (fields (field (name "PUBLISHER") "Damien Guitton"))
      (libsource (lib "DG_Mecanique") (part "Vis M3 X 6mm _TORX_Tête 6mm"))
    )
    (comp (ref "V6")
      (value "Pad_M3")
      (footprint "M3x6mm Torx")
      (description "Vis M3 X 6mm _TORX_Tête 6mm")
      (fields (field (name "PUBLISHER") "Damien Guitton"))
      (libsource (lib "DG_Mecanique") (part "Vis M3 X 6mm _TORX_Tête 6mm"))
    )
    (comp (ref "V7")
      (value "Pad_M3")
      (footprint "M3x6mm Torx")
      (description "Vis M3 X 6mm _TORX_Tête 6mm")
      (fields (field (name "PUBLISHER") "Damien Guitton"))
      (libsource (lib "DG_Mecanique") (part "Vis M3 X 6mm _TORX_Tête 6mm"))
    )
    (comp (ref "V9")
      (value "Pad_M3")
      (footprint "M3x6mm Torx")
      (description "Vis M3 X 6mm _TORX_Tête 6mm")
      (fields (field (name "PUBLISHER") "Damien Guitton"))
      (libsource (lib "DG_Mecanique") (part "Vis M3 X 6mm _TORX_Tête 6mm"))
    )
  )
  (nets
    (net (code "1") (name "/CANH") (class "Default")
      (node (ref "CANin") (pin "3") (pinfunction "3_3") (pintype "passive"))
      (node (ref "RcanH2") (pin "1") (pinfunction "1_1") (pintype "passive"))
      (node (ref "STR_Ucan") (pin "7") (pinfunction "CANH_7") (pintype "bidirectional"))
    )
    (net (code "2") (name "/CANL") (class "Default")
      (node (ref "CANin") (pin "2") (pinfunction "2_2") (pintype "passive"))
      (node (ref "RcanL2") (pin "1") (pinfunction "1_1") (pintype "passive"))
      (node (ref "STR_Ucan") (pin "6") (pinfunction "CANL_6") (pintype "bidirectional"))
    )
    (net (code "3") (name "/MaxD+") (class "Default")
      (node (ref "ACT_AX12_1") (pin "1") (pinfunction "1_1") (pintype "passive"))
      (node (ref "ACT_MAX485dif") (pin "6") (pinfunction "A_6") (pintype "bidirectional"))
      (node (ref "ACT_RX24") (pin "2") (pinfunction "2_2") (pintype "passive"))
      (node (ref "ACT_RpuMax485dif") (pin "1") (pinfunction "1_1") (pintype "passive"))
    )
    (net (code "4") (name "/MaxD-") (class "Default")
      (node (ref "ACT_MAX485dif") (pin "7") (pinfunction "~{B}_7") (pintype "bidirectional"))
      (node (ref "ACT_RX24") (pin "1") (pinfunction "1_1") (pintype "passive"))
      (node (ref "ACT_Rmax485B+") (pin "1") (pinfunction "1_1") (pintype "passive"))
      (node (ref "ACT_Rmax485B-") (pin "2") (pinfunction "2_2") (pintype "passive"))
    )
    (net (code "5") (name "/PA0_Button_RunMatch") (class "Default")
      (node (ref "STR_STM32F4DISCOVERY") (pin "12") (pinfunction "PA0-WKUP/USART2_CTS/USART4_TX/ETH_MII_CRS/TIM2_CH1_ETR/TIM5_CH1/TIM8_ETR/ADC123_IN0/WKUP_12") (pintype "passive"))
    )
    (net (code "6") (name "/PA1_CodGB") (class "Default")
      (node (ref "PRO_CcodGB") (pin "2") (pinfunction "2_2") (pintype "passive"))
      (node (ref "PRO_RCodGB") (pin "1") (pinfunction "1_1") (pintype "passive"))
      (node (ref "STR_STM32F4DISCOVERY") (pin "11") (pinfunction "PA1/USART2_RTS/USART4_RX/ETH_RMII_REF_CLK/ETH_MII_RX_CLK/TIM5_CH2/TIMM2_CH2/ADC123_IN1_11") (pintype "passive"))
    )
    (net (code "7") (name "/PA2_TX") (class "Default")
      (node (ref "STR_STM32F4DISCOVERY") (pin "14") (pinfunction "PA2/USART2_TX/TIM5_CH3/TIM9_CH1/TIM2_CH3/ETH_MDIO/ADC123_IN2_14") (pintype "passive"))
      (node (ref "UART2_RFU") (pin "2") (pinfunction "2_2") (pintype "passive"))
    )
    (net (code "8") (name "/PA3_RX") (class "Default")
      (node (ref "STR_STM32F4DISCOVERY") (pin "13") (pinfunction "PA3/USART2_RX/TIM5_CH4/TIM9_CH2/TIM2_CH4/OTG_HS_ULPI_D0/ETH_MII_COL/ADC123_IN3_13") (pintype "passive"))
      (node (ref "UART2_RFU") (pin "3") (pinfunction "3_3") (pintype "passive"))
    )
    (net (code "9") (name "/PA5_Biroute") (class "Default")
      (node (ref "CfBir") (pin "2") (pinfunction "2_2") (pintype "passive"))
      (node (ref "RsBir") (pin "2") (pinfunction "2_2") (pintype "passive"))
      (node (ref "STR_STM32F4DISCOVERY") (pin "15") (pinfunction "PA5/SPI1_SCK/OTG_HS_ULPI_CK/TIM2_CH1_ETR/TIM8_CHIN/ADC12_IN5/DAC2_OUT_15") (pintype "passive"))
    )
    (net (code "10") (name "/PA8_Sens1") (class "Default")
      (node (ref "PRO_Motors") (pin "1") (pinfunction "1_1") (pintype "passive"))
      (node (ref "STR_STM32F4DISCOVERY") (pin "93") (pinfunction "PA8/MCO1/USART1_CK/TIM1_CH1/I2C3_SCL/OTG_FS_SOF_93") (pintype "passive"))
    )
    (net (code "11") (name "/PA15_CodGA") (class "Default")
      (node (ref "PRO_CcodGA") (pin "2") (pinfunction "2_2") (pintype "passive"))
      (node (ref "PRO_RCodGA") (pin "1") (pinfunction "1_1") (pintype "passive"))
      (node (ref "STR_STM32F4DISCOVERY") (pin "90") (pinfunction "PA15/JTDI/SPI3_NSS/I2S3_WS/TIM2_CH1_ETR/SPI1_NSS_90") (pintype "passive"))
    )
    (net (code "12") (name "/PB0_AN8_Sensor0") (class "Default")
      (node (ref "STR_CfDTb0") (pin "2") (pinfunction "2_2") (pintype "passive"))
      (node (ref "STR_RfDTb0") (pin "2") (pinfunction "2_2") (pintype "passive"))
      (node (ref "STR_RpuDTb0") (pin "1") (pinfunction "1_1") (pintype "passive"))
      (node (ref "STR_STM32F4DISCOVERY") (pin "22") (pinfunction "PB0/TIM3_CH3/TIM8_CH2N/OTG_HS_ULPI_D1/ETH_MII_RXD2/TIM1_CH2N/ADC12_IN8_22") (pintype "passive"))
    )
    (net (code "13") (name "/PB1_AN9_Sensor1") (class "Default")
      (node (ref "STR_CfDTb1") (pin "2") (pinfunction "2_2") (pintype "passive"))
      (node (ref "STR_RfDTb1") (pin "2") (pinfunction "2_2") (pintype "passive"))
      (node (ref "STR_RpuDTb1") (pin "1") (pinfunction "1_1") (pintype "passive"))
      (node (ref "STR_STM32F4DISCOVERY") (pin "21") (pinfunction "PB1/TIM3_CH4/TIM_CH3N/OTG_HS_ULPI_D2/ETH_MII_RXD3/OTG_HS_INTN/TIM1_CH3N/ADC12_IN9_21") (pintype "passive"))
    )
    (net (code "14") (name "/PB2_US0_Echo") (class "Default")
      (node (ref "RUS0+") (pin "1") (pinfunction "1_1") (pintype "passive"))
      (node (ref "RUS0-") (pin "2") (pinfunction "2_2") (pintype "passive"))
      (node (ref "STR_STM32F4DISCOVERY") (pin "24") (pinfunction "PB2_24") (pintype "passive"))
    )
    (net (code "15") (name "/PB4_CodDA") (class "Default")
      (node (ref "PRO_CcodDB") (pin "2") (pinfunction "2_2") (pintype "passive"))
      (node (ref "PRO_RCodDB") (pin "1") (pinfunction "1_1") (pintype "passive"))
      (node (ref "STR_STM32F4DISCOVERY") (pin "75") (pinfunction "PB4/NJTRST/SPI3_MISO/TIM3_CH1/SPI1_MISO/I2S3ext_SD_75") (pintype "passive"))
    )
    (net (code "16") (name "/PB5_CodDB") (class "Default")
      (node (ref "PRO_CcodDA") (pin "2") (pinfunction "2_2") (pintype "passive"))
      (node (ref "PRO_RCodDA") (pin "1") (pinfunction "1_1") (pintype "passive"))
      (node (ref "STR_STM32F4DISCOVERY") (pin "76") (pinfunction "PB5/I2C1_SMBA/CAN2_RX/OTG_HS_ULPI_D7/ETH_PPS_OUT/TIM3_CH2/SPI1_MOSI/SPI3_MOSI/DCMI_D10/I2S3_SD_76") (pintype "passive"))
    )
    (net (code "17") (name "/PB6_U1TX") (class "Default")
      (node (ref "STR_RsU1tx") (pin "2") (pinfunction "2_2") (pintype "passive"))
      (node (ref "STR_STM32F4DISCOVERY") (pin "73") (pinfunction "PB6/I2C1_SCL/TIM4_CH1/CAN2_TX/OTG_FS_INTN/DCMI_D5/USART1_TX_73") (pintype "passive"))
    )
    (net (code "18") (name "/PB7_U1RX") (class "Default")
      (node (ref "STR_Cu1rx") (pin "2") (pinfunction "2_2") (pintype "passive"))
      (node (ref "STR_RpuU1rx") (pin "1") (pinfunction "1_1") (pintype "passive"))
      (node (ref "STR_Rsu1rx") (pin "1") (pinfunction "1_1") (pintype "passive"))
      (node (ref "STR_STM32F4DISCOVERY") (pin "74") (pinfunction "PB7/I2C1_SDA/FSMC_ML/DCMI_VSYNC/USART1_RX/TIM4_CH2_74") (pintype "passive"))
    )
    (net (code "19") (name "/PB8_US1_Echo") (class "Default")
      (node (ref "RUS1+") (pin "1") (pinfunction "1_1") (pintype "passive"))
      (node (ref "RUS1-") (pin "2") (pinfunction "2_2") (pintype "passive"))
      (node (ref "STR_STM32F4DISCOVERY") (pin "69") (pinfunction "PB8/TIM4_CH3/SDIO_D4/TIM10_CH1/DCMI_D6/OTG_FS_SCL/ETH_MII_TXD3/I2C1_SCL/CAN1_RX_69") (pintype "passive"))
    )
    (net (code "20") (name "/PB9_US2_Echo") (class "Default")
      (node (ref "RUS2+") (pin "1") (pinfunction "1_1") (pintype "passive"))
      (node (ref "RUS2-") (pin "2") (pinfunction "2_2") (pintype "passive"))
      (node (ref "STR_STM32F4DISCOVERY") (pin "70") (pinfunction "PB9/SPI2_NSS/I2S2_WS/TIM4_CH4/TIM11_CH1/OTG_FS_SDA/SDIO_D5/DCMI_D7/I2C1_SDA/CAN1_TX_70") (pintype "passive"))
    )
    (net (code "21") (name "/PB10_US3_Echo") (class "Default")
      (node (ref "RUS3+") (pin "1") (pinfunction "1_1") (pintype "passive"))
      (node (ref "RUS3-") (pin "2") (pinfunction "2_2") (pintype "passive"))
      (node (ref "STR_STM32F4DISCOVERY") (pin "34") (pinfunction "PB10/SPI2_SCK/I2S2_CK/I2C2_SCL/USART3_TX/OTG_HS_ULPI_D3/ETH_MII_RX_ER/OTG_HS_SCL/TIM2_CH3_34") (pintype "passive"))
    )
    (net (code "22") (name "/PB11_MAX485_Sens") (class "Default")
      (node (ref "ACT_MAX485dif") (pin "2") (pinfunction "~{RE}_2") (pintype "input"))
      (node (ref "ACT_MAX485dif") (pin "3") (pinfunction "DE_3") (pintype "input"))
      (node (ref "STR_STM32F4DISCOVERY") (pin "35") (pinfunction "PB11/I2C2_SDA/USART3_RX/OTG_HS_ULPI_D4/ETH_RMII_TX_EN/ETH_MII_TX_EN/OTG_HS_SDA/TIM2_CH4_35") (pintype "passive"))
    )
    (net (code "23") (name "/PB12_US0_Trigger") (class "Default")
      (node (ref "STR_STM32F4DISCOVERY") (pin "36") (pinfunction "PB12/SPI2_NSS/I2S2_WS/I2C2_SMBA/USART3_CK/TIM1_BKIN/CAN2_RX/OTG_HS_ULPI_D5/ETH_RMII_TXD0/ETH_MII_TXD0/OTG_HS_ID_36") (pintype "passive"))
      (node (ref "US0") (pin "3") (pinfunction "3_3") (pintype "passive"))
    )
    (net (code "24") (name "/PB13_US1_Trigger") (class "Default")
      (node (ref "STR_STM32F4DISCOVERY") (pin "37") (pinfunction "PB13/SPI2_SCK/I2S2_CK/USART3_CTS/TIM1_CH1N/CAN2_TX/OTG_HS_ULPI_D6/ETH_RMII_TXD1/ETH_MII_TXD1/OTG_HS_VBUS_37") (pintype "passive"))
      (node (ref "US1") (pin "3") (pinfunction "3_3") (pintype "passive"))
    )
    (net (code "25") (name "/PB14_US2_Trigger") (class "Default")
      (node (ref "STR_STM32F4DISCOVERY") (pin "38") (pinfunction "PB14/SPI2_MISO/TIM1_CH2N/TIM12_CH1/OTG_HS_DMUSART3_RTS/TIM8_CH2N/I2S2ext_SD_38") (pintype "passive"))
      (node (ref "US2") (pin "3") (pinfunction "3_3") (pintype "passive"))
    )
    (net (code "26") (name "/PB15_US3_Trigger") (class "Default")
      (node (ref "STR_STM32F4DISCOVERY") (pin "39") (pinfunction "PB15/SPI2_MOSI/I2S2_SD/TIM1_CH3N/TIM8_CH3N/TIM12_CH2/OTG_HS_DP_39") (pintype "passive"))
      (node (ref "US3") (pin "3") (pinfunction "3_3") (pintype "passive"))
    )
    (net (code "27") (name "/PC1_AN11_Sensor2") (class "Default")
      (node (ref "STR_CfDTc1") (pin "2") (pinfunction "2_2") (pintype "passive"))
      (node (ref "STR_RfDTc1") (pin "2") (pinfunction "2_2") (pintype "passive"))
      (node (ref "STR_RpuDTc1") (pin "1") (pinfunction "1_1") (pintype "passive"))
      (node (ref "STR_STM32F4DISCOVERY") (pin "7") (pinfunction "PC1/ETH_MDC/ADC123_IN11_7") (pintype "passive"))
    )
    (net (code "28") (name "/PC2_AN12_Sensor3") (class "Default")
      (node (ref "STR_CfDTc2") (pin "2") (pinfunction "2_2") (pintype "passive"))
      (node (ref "STR_RfDTc2") (pin "2") (pinfunction "2_2") (pintype "passive"))
      (node (ref "STR_RpuDTc2") (pin "1") (pinfunction "1_1") (pintype "passive"))
      (node (ref "STR_STM32F4DISCOVERY") (pin "10") (pinfunction "PC2/SPI2_MISO/OTG_HS_ULPI_DIR/TH_MII_TXD2/I2S2ext_SD/ADC123_IN12_10") (pintype "passive"))
    )
    (net (code "29") (name "/PC4_AN14_Sensor4") (class "Default")
      (node (ref "STR_CfDTc4") (pin "2") (pinfunction "2_2") (pintype "passive"))
      (node (ref "STR_RfDTc4") (pin "2") (pinfunction "2_2") (pintype "passive"))
      (node (ref "STR_RpuDTc4") (pin "1") (pinfunction "1_1") (pintype "passive"))
      (node (ref "STR_STM32F4DISCOVERY") (pin "20") (pinfunction "PC4/ETH_RMII_RX_D0/ETH_MII_RX_D0/ADC12_IN14_20") (pintype "passive"))
    )
    (net (code "30") (name "/PC6_PWM1") (class "Default")
      (node (ref "PRO_Motors") (pin "2") (pinfunction "2_2") (pintype "passive"))
      (node (ref "STR_STM32F4DISCOVERY") (pin "97") (pinfunction "PC6/I2S2_MCK/TIM8_CH1/SDIO_D6/USART6_TX/DCMI_D0/TIM3_CH1_97") (pintype "passive"))
    )
    (net (code "31") (name "/PC7_PWM2") (class "Default")
      (node (ref "PRO_Motors") (pin "5") (pinfunction "5_5") (pintype "passive"))
      (node (ref "STR_STM32F4DISCOVERY") (pin "98") (pinfunction "PC7/I2S3_MCK/TIM8_CH2/SDIO_D7/USART6_RX_DCMI_D1/TIM3_CH2_98") (pintype "passive"))
    )
    (net (code "32") (name "/PC8_Motor_Right_Pulse") (class "Default")
      (node (ref "Motor_Right") (pin "6") (pinfunction "6_6") (pintype "passive"))
      (node (ref "STR_STM32F4DISCOVERY") (pin "95") (pinfunction "PC8/TIM8_CH3/SDIO_D0/TIM3_CH3/USART6_CK/DCMI_D2_95") (pintype "passive"))
    )
    (net (code "33") (name "/PC9_Motor_Left_Pulse") (class "Default")
      (node (ref "Motor_Left") (pin "6") (pinfunction "6_6") (pintype "passive"))
      (node (ref "STR_STM32F4DISCOVERY") (pin "96") (pinfunction "PC9/I2S_CKIN/MCO2/TIM8_CH4/SDIO_D1/I2C3_SDA/DCMI_D3/TIM3_CH4_96") (pintype "passive"))
    )
    (net (code "34") (name "/PC10_Motor_Enable") (class "Default")
      (node (ref "Motor_Left") (pin "4") (pinfunction "4_4") (pintype "passive"))
      (node (ref "Motor_Right") (pin "4") (pinfunction "4_4") (pintype "passive"))
      (node (ref "STR_STM32F4DISCOVERY") (pin "87") (pinfunction "PC10/SPI3_SCK/I2S3_CK/UART4_TX/SDIO_D2/DCMI_D8/USART3_TX_87") (pintype "passive"))
    )
    (net (code "35") (name "/PC11_Motor_Right_Dir") (class "Default")
      (node (ref "Motor_Right") (pin "5") (pinfunction "5_5") (pintype "passive"))
      (node (ref "STR_STM32F4DISCOVERY") (pin "88") (pinfunction "PC11/UART4_RX/SPI3_MISO/SDIO_D3/DCMI_D4/USART3_RX/I2S3ext_SD_88") (pintype "passive"))
    )
    (net (code "36") (name "/PC12_Motor_Left_Dir") (class "Default")
      (node (ref "Motor_Left") (pin "5") (pinfunction "5_5") (pintype "passive"))
      (node (ref "STR_STM32F4DISCOVERY") (pin "85") (pinfunction "PC12/UART5_TX/SDIO_CK/DCMI_D9/SPI3_MOSI/I2S3_SD/USART3_CK_85") (pintype "passive"))
    )
    (net (code "37") (name "/PD0_CANRX") (class "Default")
      (node (ref "STR_STM32F4DISCOVERY") (pin "86") (pinfunction "PD0/FSMC_D2/CAN1_RX_86") (pintype "passive"))
      (node (ref "STR_Ucan") (pin "4") (pinfunction "RXD_4") (pintype "output"))
    )
    (net (code "38") (name "/PD1_CANTX") (class "Default")
      (node (ref "STR_STM32F4DISCOVERY") (pin "83") (pinfunction "PD1/FSMC_D3/CAN1_TX_83") (pintype "passive"))
      (node (ref "STR_Ucan") (pin "1") (pinfunction "TXD_1") (pintype "input"))
    )
    (net (code "39") (name "/PD2_LED_Green") (class "Default")
      (node (ref "RGreen") (pin "1") (pinfunction "1_1") (pintype "passive"))
      (node (ref "STR_STM32F4DISCOVERY") (pin "84") (pinfunction "PD2/TIM3_ETR/UART5_RXSDIO_CMD/DCMI_D11_84") (pintype "passive"))
    )
    (net (code "40") (name "/PD3_LED_Red") (class "Default")
      (node (ref "Rred") (pin "1") (pinfunction "1_1") (pintype "passive"))
      (node (ref "STR_STM32F4DISCOVERY") (pin "81") (pinfunction "PD3/FSMC_CLK/USART2_CTS_81") (pintype "passive"))
    )
    (net (code "41") (name "/PD6_LED_Blue") (class "Default")
      (node (ref "RBlue") (pin "1") (pinfunction "1_1") (pintype "passive"))
      (node (ref "STR_STM32F4DISCOVERY") (pin "80") (pinfunction "PD6/FSMC_NWAIT/USART2_RX_80") (pintype "passive"))
    )
    (net (code "42") (name "/PD7_Sens2") (class "Default")
      (node (ref "PRO_Motors") (pin "6") (pinfunction "6_6") (pintype "passive"))
      (node (ref "STR_STM32F4DISCOVERY") (pin "77") (pinfunction "PD7/USART2_CK/FSMC_NE1/FSMC_NCE2_77") (pintype "passive"))
    )
    (net (code "43") (name "/PD8_MAX485dif_TX") (class "Default")
      (node (ref "ACT_MAX485dif") (pin "4") (pinfunction "DI_4") (pintype "input"))
      (node (ref "STR_STM32F4DISCOVERY") (pin "40") (pinfunction "PD8/FSMC_D13/USART3_TX_40") (pintype "passive"))
    )
    (net (code "44") (name "/PD9_MAX485dif_RX") (class "Default")
      (node (ref "ACT_MAX485dif") (pin "1") (pinfunction "RO_1") (pintype "tri_state"))
      (node (ref "STR_STM32F4DISCOVERY") (pin "41") (pinfunction "PD9/FSMC_D14/USART3_RX_41") (pintype "passive"))
    )
    (net (code "45") (name "/PD10_LED0") (class "Default")
      (node (ref "Rled0") (pin "2") (pinfunction "2_2") (pintype "passive"))
      (node (ref "STR_STM32F4DISCOVERY") (pin "42") (pinfunction "PD10/FSMC_D15/USART3_CK_42") (pintype "passive"))
    )
    (net (code "46") (name "/PD11_LED1") (class "Default")
      (node (ref "Rled1") (pin "2") (pinfunction "2_2") (pintype "passive"))
      (node (ref "STR_STM32F4DISCOVERY") (pin "43") (pinfunction "PD11/FSMC_A16/USART3_CTS_43") (pintype "passive"))
    )
    (net (code "47") (name "/PE0_SW0") (class "Default")
      (node (ref "CfSW0") (pin "2") (pinfunction "2_2") (pintype "passive"))
      (node (ref "RsSW0") (pin "2") (pinfunction "2_2") (pintype "passive"))
      (node (ref "STR_STM32F4DISCOVERY") (pin "67") (pinfunction "PE0/TIM4_ETR/FSMC_NBL0/DCMI_D2_67") (pintype "passive"))
    )
    (net (code "48") (name "/PE1_SW1") (class "Default")
      (node (ref "CfSW1") (pin "2") (pinfunction "2_2") (pintype "passive"))
      (node (ref "RsSW1") (pin "2") (pinfunction "2_2") (pintype "passive"))
      (node (ref "STR_STM32F4DISCOVERY") (pin "68") (pinfunction "PE1/FSMC_NBL1/DCMI_D3_68") (pintype "passive"))
    )
    (net (code "49") (name "/PE3_SW2") (class "Default")
      (node (ref "CfSW2") (pin "2") (pinfunction "2_2") (pintype "passive"))
      (node (ref "RsSW2") (pin "2") (pinfunction "2_2") (pintype "passive"))
      (node (ref "STR_STM32F4DISCOVERY") (pin "66") (pinfunction "PE3/TRACED0/FSMC_A19_66") (pintype "passive"))
    )
    (net (code "50") (name "/PE4_SW3") (class "Default")
      (node (ref "CfSW10") (pin "2") (pinfunction "2_2") (pintype "passive"))
      (node (ref "RsSW10") (pin "2") (pinfunction "2_2") (pintype "passive"))
      (node (ref "STR_STM32F4DISCOVERY") (pin "63") (pinfunction "PE4/TRACED1/FSMC_A20/DCMI_D4_63") (pintype "passive"))
    )
    (net (code "51") (name "/PE5_SW4") (class "Default")
      (node (ref "CfSW11") (pin "2") (pinfunction "2_2") (pintype "passive"))
      (node (ref "RsSW11") (pin "2") (pinfunction "2_2") (pintype "passive"))
      (node (ref "STR_STM32F4DISCOVERY") (pin "64") (pinfunction "PE5/TRACED2/FSMC_A21/TIM9_CH1/DCMI_D6_64") (pintype "passive"))
    )
    (net (code "52") (name "/PE6_SW5") (class "Default")
      (node (ref "CfSW12") (pin "2") (pinfunction "2_2") (pintype "passive"))
      (node (ref "RsSW12") (pin "2") (pinfunction "2_2") (pintype "passive"))
      (node (ref "STR_STM32F4DISCOVERY") (pin "61") (pinfunction "PE6/TRACED3/FSMC_A22/TIM9_CH2/DCMI_D7_61") (pintype "passive"))
    )
    (net (code "53") (name "/PE7_I_AM") (class "Default")
      (node (ref "STR_STM32F4DISCOVERY") (pin "25") (pinfunction "PE7/FSMC_D4/TIM1_ETR_25") (pintype "passive"))
      (node (ref "st_i_am_pe7") (pin "2") (pinfunction "2_2") (pintype "passive"))
    )
    (net (code "54") (name "/PE8_I_AM") (class "Default")
      (node (ref "STR_STM32F4DISCOVERY") (pin "26") (pinfunction "PE8/FSMC_D5/TIM1_CH1N_26") (pintype "passive"))
      (node (ref "st_i_am_pe8") (pin "2") (pinfunction "2_2") (pintype "passive"))
    )
    (net (code "55") (name "/PE9_I_AM") (class "Default")
      (node (ref "STR_STM32F4DISCOVERY") (pin "27") (pinfunction "PE9/FSMC_D6/TIM1_CH1_27") (pintype "passive"))
      (node (ref "st_i_am_pe9") (pin "2") (pinfunction "2_2") (pintype "passive"))
    )
    (net (code "56") (name "/PE10_BP0") (class "Default")
      (node (ref "CfBP0") (pin "2") (pinfunction "2_2") (pintype "passive"))
      (node (ref "RsBP0") (pin "2") (pinfunction "2_2") (pintype "passive"))
      (node (ref "STR_STM32F4DISCOVERY") (pin "28") (pinfunction "PE10/FSMC_D7/TIM1_CH2N_28") (pintype "passive"))
    )
    (net (code "57") (name "/PE12_BP1") (class "Default")
      (node (ref "CfBP1") (pin "2") (pinfunction "2_2") (pintype "passive"))
      (node (ref "RsBP1") (pin "2") (pinfunction "2_2") (pintype "passive"))
      (node (ref "STR_STM32F4DISCOVERY") (pin "30") (pinfunction "PE12/FSMC_D9/TIM1_CH3N_30") (pintype "passive"))
    )
    (net (code "58") (name "/PE13_servo0") (class "Default")
      (node (ref "STR_STM32F4DISCOVERY") (pin "31") (pinfunction "PE13/FSMC_D10/TIM1_CH3_31") (pintype "passive"))
      (node (ref "Servo0") (pin "3") (pinfunction "3_3") (pintype "passive"))
    )
    (net (code "59") (name "/PE14_BP2") (class "Default")
      (node (ref "CfBP2") (pin "2") (pinfunction "2_2") (pintype "passive"))
      (node (ref "RsBP2") (pin "2") (pinfunction "2_2") (pintype "passive"))
      (node (ref "STR_STM32F4DISCOVERY") (pin "32") (pinfunction "PE14/FSMC_D11/TIM1_CH4_32") (pintype "passive"))
    )
    (net (code "60") (name "/PE15_BP3") (class "Default")
      (node (ref "CfBP3") (pin "2") (pinfunction "2_2") (pintype "passive"))
      (node (ref "RsBP3") (pin "2") (pinfunction "2_2") (pintype "passive"))
      (node (ref "STR_STM32F4DISCOVERY") (pin "33") (pinfunction "PE15/FSMC_D12/TIM1_BKIN_33") (pintype "passive"))
    )
    (net (code "61") (name "/STR_PD12_RUN") (class "Default")
      (node (ref "STR_STM32F4DISCOVERY") (pin "44") (pinfunction "PD12/FSMC_A17/TIM4_CH1/USART3_RTS_44") (pintype "passive"))
    )
    (net (code "62") (name "/STR_PD13_CAN") (class "Default")
      (node (ref "STR_STM32F4DISCOVERY") (pin "45") (pinfunction "PD13/FSMC_A18/TIM4_CH2_45") (pintype "passive"))
    )
    (net (code "63") (name "/STR_PD14_UART") (class "Default")
      (node (ref "STR_STM32F4DISCOVERY") (pin "46") (pinfunction "PD14/FSMC_D0/TIM4_CH3_46") (pintype "passive"))
    )
    (net (code "64") (name "/STR_PD15_USER") (class "Default")
      (node (ref "STR_STM32F4DISCOVERY") (pin "47") (pinfunction "PD15/FSMC_D1/TIM4_CH4_47") (pintype "passive"))
    )
    (net (code "65") (name "/STR_U1RX") (class "Default")
      (node (ref "STR_Rsu1rx") (pin "2") (pinfunction "2_2") (pintype "passive"))
      (node (ref "STR_UART1") (pin "4") (pinfunction "4_4") (pintype "passive"))
    )
    (net (code "66") (name "/STR_U1TX") (class "Default")
      (node (ref "STR_RpuU1tx") (pin "1") (pinfunction "1_1") (pintype "passive"))
      (node (ref "STR_RsU1tx") (pin "1") (pinfunction "1_1") (pintype "passive"))
      (node (ref "STR_UART1") (pin "3") (pinfunction "3_3") (pintype "passive"))
    )
    (net (code "67") (name "3V") (class "Default")
      (node (ref "RpuBP0") (pin "2") (pinfunction "2_2") (pintype "passive"))
      (node (ref "RpuBP1") (pin "2") (pinfunction "2_2") (pintype "passive"))
      (node (ref "RpuBP2") (pin "2") (pinfunction "2_2") (pintype "passive"))
      (node (ref "RpuBP3") (pin "2") (pinfunction "2_2") (pintype "passive"))
      (node (ref "RpuSW0") (pin "2") (pinfunction "2_2") (pintype "passive"))
      (node (ref "RpuSW1") (pin "2") (pinfunction "2_2") (pintype "passive"))
      (node (ref "RpuSW10") (pin "2") (pinfunction "2_2") (pintype "passive"))
      (node (ref "RpuSW11") (pin "2") (pinfunction "2_2") (pintype "passive"))
      (node (ref "RpuSW12") (pin "2") (pinfunction "2_2") (pintype "passive"))
      (node (ref "RpuSW2") (pin "2") (pinfunction "2_2") (pintype "passive"))
      (node (ref "STR_RpuDTb0") (pin "2") (pinfunction "2_2") (pintype "passive"))
      (node (ref "STR_RpuDTb1") (pin "2") (pinfunction "2_2") (pintype "passive"))
      (node (ref "STR_RpuDTc1") (pin "2") (pinfunction "2_2") (pintype "passive"))
      (node (ref "STR_RpuDTc2") (pin "2") (pinfunction "2_2") (pintype "passive"))
      (node (ref "STR_RpuDTc4") (pin "2") (pinfunction "2_2") (pintype "passive"))
      (node (ref "STR_RpuU1rx") (pin "2") (pinfunction "2_2") (pintype "passive"))
      (node (ref "STR_RpuU1tx") (pin "2") (pinfunction "2_2") (pintype "passive"))
      (node (ref "STR_STM32F4DISCOVERY") (pin "55") (pinfunction "3V_55") (pintype "passive"))
      (node (ref "STR_STM32F4DISCOVERY") (pin "56") (pinfunction "3V_56") (pintype "passive"))
    )
    (net (code "68") (name "5V") (class "Default")
      (node (ref "ACT_CdMax485dif") (pin "2") (pinfunction "2_2") (pintype "passive"))
      (node (ref "ACT_MAX485dif") (pin "8") (pinfunction "VCC_8") (pintype "passive"))
      (node (ref "ACT_Rmax485B+") (pin "2") (pinfunction "2_2") (pintype "passive"))
      (node (ref "ACT_RpuMax485dif") (pin "2") (pinfunction "2_2") (pintype "passive"))
      (node (ref "Cde_out") (pin "1") (pinfunction "1_1") (pintype "passive"))
      (node (ref "LED_color") (pin "1") (pinfunction "A_1") (pintype "passive"))
      (node (ref "PRO_codDroite") (pin "1") (pinfunction "1_1") (pintype "passive"))
      (node (ref "PRO_codDroite") (pin "2") (pinfunction "2_2") (pintype "passive"))
      (node (ref "PRO_codGauche") (pin "1") (pinfunction "1_1") (pintype "passive"))
      (node (ref "PRO_codGauche") (pin "2") (pinfunction "2_2") (pintype "passive"))
      (node (ref "Rcde") (pin "1") (pinfunction "1_1") (pintype "passive"))
      (node (ref "RledBir") (pin "2") (pinfunction "2_2") (pintype "passive"))
      (node (ref "RpuBir") (pin "2") (pinfunction "2_2") (pintype "passive"))
      (node (ref "RsLedBP0") (pin "2") (pinfunction "2_2") (pintype "passive"))
      (node (ref "RsLedBP1") (pin "2") (pinfunction "2_2") (pintype "passive"))
      (node (ref "RsLedBP2") (pin "2") (pinfunction "2_2") (pintype "passive"))
      (node (ref "RsLedBP3") (pin "2") (pinfunction "2_2") (pintype "passive"))
      (node (ref "STR_CdCan1") (pin "2") (pinfunction "2_2") (pintype "passive"))
      (node (ref "STR_CdCan2") (pin "2") (pinfunction "2_2") (pintype "passive"))
      (node (ref "STR_STM32F4DISCOVERY") (pin "53") (pinfunction "5V_53") (pintype "passive"))
      (node (ref "STR_STM32F4DISCOVERY") (pin "54") (pinfunction "5V_54") (pintype "passive"))
      (node (ref "STR_Ucan") (pin "3") (pinfunction "VDD_3") (pintype "power_in"))
      (node (ref "Servo0") (pin "2") (pinfunction "2_2") (pintype "passive"))
      (node (ref "UART2_RFU") (pin "4") (pinfunction "4_4") (pintype "passive"))
      (node (ref "US0") (pin "4") (pinfunction "4_4") (pintype "passive"))
      (node (ref "US1") (pin "4") (pinfunction "4_4") (pintype "passive"))
      (node (ref "US2") (pin "4") (pinfunction "4_4") (pintype "passive"))
      (node (ref "US3") (pin "4") (pinfunction "4_4") (pintype "passive"))
    )
    (net (code "69") (name "5VPerm") (class "Default")
      (node (ref "CdPerm") (pin "2") (pinfunction "2_2") (pintype "passive"))
      (node (ref "Cde_in") (pin "1") (pinfunction "1_1") (pintype "passive"))
      (node (ref "STR_UART1") (pin "1") (pinfunction "1_1") (pintype "passive"))
      (node (ref "STR_UART1") (pin "2") (pinfunction "2_2") (pintype "passive"))
      (node (ref "TR_5V") (pin "3") (pinfunction "+Vout1_3") (pintype "passive"))
    )
    (net (code "70") (name "12V") (class "Default")
      (node (ref "12V") (pin "2") (pinfunction "2_2") (pintype "passive"))
      (node (ref "12V_T12") (pin "1") (pinfunction "1_1") (pintype "passive"))
      (node (ref "ACT_AX12_1") (pin "2") (pinfunction "2_2") (pintype "passive"))
      (node (ref "ACT_RX24") (pin "3") (pinfunction "3_3") (pintype "passive"))
      (node (ref "Rhok") (pin "1") (pinfunction "1_1") (pintype "passive"))
    )
    (net (code "71") (name "24VPsce") (class "Default")
      (node (ref "24V_T12") (pin "1") (pinfunction "1_1") (pintype "passive"))
      (node (ref "ARU_out") (pin "1") (pinfunction "1_1") (pintype "passive"))
      (node (ref "J5_24V") (pin "2") (pinfunction "2_2") (pintype "passive"))
      (node (ref "Motor_Left") (pin "2") (pinfunction "2_2") (pintype "passive"))
      (node (ref "Motor_Right") (pin "2") (pinfunction "2_2") (pintype "passive"))
      (node (ref "R24Psce") (pin "1") (pinfunction "1_1") (pintype "passive"))
      (node (ref "STR_CdDtb0") (pin "2") (pinfunction "2_2") (pintype "passive"))
      (node (ref "STR_CdDtb1") (pin "2") (pinfunction "2_2") (pintype "passive"))
      (node (ref "STR_CdDtc1") (pin "2") (pinfunction "2_2") (pintype "passive"))
      (node (ref "STR_CdDtc2") (pin "2") (pinfunction "2_2") (pintype "passive"))
      (node (ref "STR_CdDtc4") (pin "2") (pinfunction "2_2") (pintype "passive"))
      (node (ref "Sensor0") (pin "3") (pinfunction "3_3") (pintype "passive"))
      (node (ref "Sensor1") (pin "3") (pinfunction "3_3") (pintype "passive"))
      (node (ref "Sensor2") (pin "3") (pinfunction "3_3") (pintype "passive"))
      (node (ref "Sensor3") (pin "3") (pinfunction "3_3") (pintype "passive"))
      (node (ref "Sensor4") (pin "3") (pinfunction "3_3") (pintype "passive"))
    )
    (net (code "72") (name "24Vperm") (class "Default")
      (node (ref "BAT_24V") (pin "1") (pinfunction "1_1") (pintype "passive"))
      (node (ref "Dreverse") (pin "1") (pinfunction "A1_1") (pintype "passive"))
      (node (ref "Dreverse") (pin "3") (pinfunction "A2_3") (pintype "passive"))
      (node (ref "R24in") (pin "1") (pinfunction "1_1") (pintype "passive"))
    )
    (net (code "73") (name "GND") (class "Default")
      (node (ref "ACT_CdMax485dif") (pin "1") (pinfunction "1_1") (pintype "passive"))
      (node (ref "ACT_MAX485dif") (pin "5") (pinfunction "GND_5") (pintype "passive"))
      (node (ref "ACT_Rmax485B-") (pin "1") (pinfunction "1_1") (pintype "passive"))
      (node (ref "BP0") (pin "1") (pinfunction "1_1") (pintype "passive"))
      (node (ref "BP0") (pin "3") (pinfunction "3_3") (pintype "passive"))
      (node (ref "BP0") (pin "6") (pinfunction "-_6") (pintype "passive"))
      (node (ref "BP1") (pin "1") (pinfunction "1_1") (pintype "passive"))
      (node (ref "BP1") (pin "3") (pinfunction "3_3") (pintype "passive"))
      (node (ref "BP1") (pin "6") (pinfunction "-_6") (pintype "passive"))
      (node (ref "BP2") (pin "1") (pinfunction "1_1") (pintype "passive"))
      (node (ref "BP2") (pin "3") (pinfunction "3_3") (pintype "passive"))
      (node (ref "BP2") (pin "6") (pinfunction "-_6") (pintype "passive"))
      (node (ref "BP3") (pin "1") (pinfunction "1_1") (pintype "passive"))
      (node (ref "BP3") (pin "3") (pinfunction "3_3") (pintype "passive"))
      (node (ref "BP3") (pin "6") (pinfunction "-_6") (pintype "passive"))
      (node (ref "CANin") (pin "1") (pinfunction "1_1") (pintype "passive"))
      (node (ref "CANin") (pin "4") (pinfunction "4_4") (pintype "passive"))
      (node (ref "CdPerm") (pin "1") (pinfunction "1_1") (pintype "passive"))
      (node (ref "CfBP0") (pin "1") (pinfunction "1_1") (pintype "passive"))
      (node (ref "CfBP1") (pin "1") (pinfunction "1_1") (pintype "passive"))
      (node (ref "CfBP2") (pin "1") (pinfunction "1_1") (pintype "passive"))
      (node (ref "CfBP3") (pin "1") (pinfunction "1_1") (pintype "passive"))
      (node (ref "CfBir") (pin "1") (pinfunction "1_1") (pintype "passive"))
      (node (ref "CfSW0") (pin "1") (pinfunction "1_1") (pintype "passive"))
      (node (ref "CfSW1") (pin "1") (pinfunction "1_1") (pintype "passive"))
      (node (ref "CfSW10") (pin "1") (pinfunction "1_1") (pintype "passive"))
      (node (ref "CfSW11") (pin "1") (pinfunction "1_1") (pintype "passive"))
      (node (ref "CfSW12") (pin "1") (pinfunction "1_1") (pintype "passive"))
      (node (ref "CfSW2") (pin "1") (pinfunction "1_1") (pintype "passive"))
      (node (ref "Dcde") (pin "2") (pinfunction "K_2") (pintype "passive"))
      (node (ref "Led0") (pin "2") (pinfunction "K_2") (pintype "passive"))
      (node (ref "Led1") (pin "2") (pinfunction "K_2") (pintype "passive"))
      (node (ref "Motor_Left") (pin "3") (pinfunction "3_3") (pintype "passive"))
      (node (ref "Motor_Right") (pin "3") (pinfunction "3_3") (pintype "passive"))
      (node (ref "PRO_CcodDA") (pin "1") (pinfunction "1_1") (pintype "passive"))
      (node (ref "PRO_CcodDB") (pin "1") (pinfunction "1_1") (pintype "passive"))
      (node (ref "PRO_CcodGA") (pin "1") (pinfunction "1_1") (pintype "passive"))
      (node (ref "PRO_CcodGB") (pin "1") (pinfunction "1_1") (pintype "passive"))
      (node (ref "PRO_Motors") (pin "3") (pinfunction "3_3") (pintype "passive"))
      (node (ref "PRO_Motors") (pin "4") (pinfunction "4_4") (pintype "passive"))
      (node (ref "PRO_codDroite") (pin "5") (pinfunction "5_5") (pintype "passive"))
      (node (ref "PRO_codDroite") (pin "6") (pinfunction "6_6") (pintype "passive"))
      (node (ref "PRO_codGauche") (pin "5") (pinfunction "5_5") (pintype "passive"))
      (node (ref "PRO_codGauche") (pin "6") (pinfunction "6_6") (pintype "passive"))
      (node (ref "RUS0-") (pin "1") (pinfunction "1_1") (pintype "passive"))
      (node (ref "RUS1-") (pin "1") (pinfunction "1_1") (pintype "passive"))
      (node (ref "RUS2-") (pin "1") (pinfunction "1_1") (pintype "passive"))
      (node (ref "RUS3-") (pin "1") (pinfunction "1_1") (pintype "passive"))
      (node (ref "RcanH2") (pin "2") (pinfunction "2_2") (pintype "passive"))
      (node (ref "RcanL2") (pin "2") (pinfunction "2_2") (pintype "passive"))
      (node (ref "STR_CdCan1") (pin "1") (pinfunction "1_1") (pintype "passive"))
      (node (ref "STR_CdCan2") (pin "1") (pinfunction "1_1") (pintype "passive"))
      (node (ref "STR_CfDTb0") (pin "1") (pinfunction "1_1") (pintype "passive"))
      (node (ref "STR_CfDTb1") (pin "1") (pinfunction "1_1") (pintype "passive"))
      (node (ref "STR_CfDTc1") (pin "1") (pinfunction "1_1") (pintype "passive"))
      (node (ref "STR_CfDTc2") (pin "1") (pinfunction "1_1") (pintype "passive"))
      (node (ref "STR_CfDTc4") (pin "1") (pinfunction "1_1") (pintype "passive"))
      (node (ref "STR_Cu1rx") (pin "1") (pinfunction "1_1") (pintype "passive"))
      (node (ref "STR_Rdtb0") (pin "1") (pinfunction "1_1") (pintype "passive"))
      (node (ref "STR_Rdtb1") (pin "1") (pinfunction "1_1") (pintype "passive"))
      (node (ref "STR_Rdtc1") (pin "1") (pinfunction "1_1") (pintype "passive"))
      (node (ref "STR_Rdtc2") (pin "1") (pinfunction "1_1") (pintype "passive"))
      (node (ref "STR_Rdtc4") (pin "1") (pinfunction "1_1") (pintype "passive"))
      (node (ref "STR_STM32F4DISCOVERY") (pin "1") (pinfunction "GND_1") (pintype "passive"))
      (node (ref "STR_STM32F4DISCOVERY") (pin "100") (pinfunction "GND_100") (pintype "passive"))
      (node (ref "STR_STM32F4DISCOVERY") (pin "2") (pinfunction "GND_2") (pintype "passive"))
      (node (ref "STR_STM32F4DISCOVERY") (pin "23") (pinfunction "GND_23") (pintype "passive"))
      (node (ref "STR_STM32F4DISCOVERY") (pin "49") (pinfunction "GND_49") (pintype "passive"))
      (node (ref "STR_STM32F4DISCOVERY") (pin "5") (pinfunction "GND_5") (pintype "passive"))
      (node (ref "STR_STM32F4DISCOVERY") (pin "50") (pinfunction "GND_50") (pintype "passive"))
      (node (ref "STR_STM32F4DISCOVERY") (pin "51") (pinfunction "GND_51") (pintype "passive"))
      (node (ref "STR_STM32F4DISCOVERY") (pin "52") (pinfunction "GND_52") (pintype "passive"))
      (node (ref "STR_STM32F4DISCOVERY") (pin "99") (pinfunction "GND_99") (pintype "passive"))
      (node (ref "STR_UART1") (pin "5") (pinfunction "5_5") (pintype "passive"))
      (node (ref "STR_UART1") (pin "6") (pinfunction "6_6") (pintype "passive"))
      (node (ref "STR_Ucan") (pin "2") (pinfunction "VSS_2") (pintype "power_in"))
      (node (ref "STR_Ucan") (pin "8") (pinfunction "RS_8") (pintype "input"))
      (node (ref "STgnd24") (pin "2") (pinfunction "2_2") (pintype "passive"))
      (node (ref "SW0") (pin "COMMON1") (pinfunction "COMMON1_COMMON1") (pintype "passive"))
      (node (ref "SW1") (pin "COMMON1") (pinfunction "COMMON1_COMMON1") (pintype "passive"))
      (node (ref "SW10") (pin "COMMON1") (pinfunction "COMMON1_COMMON1") (pintype "passive"))
      (node (ref "SW11") (pin "COMMON1") (pinfunction "COMMON1_COMMON1") (pintype "passive"))
      (node (ref "SW12") (pin "COMMON1") (pinfunction "COMMON1_COMMON1") (pintype "passive"))
      (node (ref "SW2") (pin "COMMON1") (pinfunction "COMMON1_COMMON1") (pintype "passive"))
      (node (ref "TR_5V") (pin "5") (pinfunction "-Vout1_5") (pintype "passive"))
      (node (ref "UART2_RFU") (pin "1") (pinfunction "1_1") (pintype "passive"))
      (node (ref "US0") (pin "1") (pinfunction "1_1") (pintype "passive"))
      (node (ref "US1") (pin "1") (pinfunction "1_1") (pintype "passive"))
      (node (ref "US2") (pin "1") (pinfunction "1_1") (pintype "passive"))
      (node (ref "US3") (pin "1") (pinfunction "1_1") (pintype "passive"))
      (node (ref "V4") (pin "1") (pinfunction "1_1") (pintype "passive"))
      (node (ref "V6") (pin "1") (pinfunction "1_1") (pintype "passive"))
      (node (ref "V7") (pin "1") (pinfunction "1_1") (pintype "passive"))
      (node (ref "V9") (pin "1") (pinfunction "1_1") (pintype "passive"))
      (node (ref "biroute_gnd") (pin "1") (pinfunction "1_1") (pintype "passive"))
      (node (ref "st_i_am_pe7") (pin "1") (pinfunction "1_1") (pintype "passive"))
      (node (ref "st_i_am_pe8") (pin "1") (pinfunction "1_1") (pintype "passive"))
      (node (ref "st_i_am_pe9") (pin "1") (pinfunction "1_1") (pintype "passive"))
    )
    (net (code "74") (name "GND_5") (class "Default")
      (node (ref "Servo0") (pin "1") (pinfunction "1_1") (pintype "passive"))
    )
    (net (code "75") (name "GND_12") (class "Default")
      (node (ref "12V") (pin "1") (pinfunction "1_1") (pintype "passive"))
      (node (ref "ACT_AX12_1") (pin "3") (pinfunction "3_3") (pintype "passive"))
      (node (ref "ACT_RX24") (pin "4") (pinfunction "4_4") (pintype "passive"))
      (node (ref "Dhok") (pin "2") (pinfunction "K_2") (pintype "passive"))
      (node (ref "STgnd12") (pin "1") (pinfunction "1_1") (pintype "passive"))
    )
    (net (code "76") (name "GND_24") (class "Default")
      (node (ref "BAT_GND") (pin "1") (pinfunction "1_1") (pintype "passive"))
      (node (ref "Cd24VCDE") (pin "1") (pinfunction "1_1") (pintype "passive"))
      (node (ref "D24Psce") (pin "2") (pinfunction "K_2") (pintype "passive"))
      (node (ref "D24in") (pin "2") (pinfunction "K_2") (pintype "passive"))
      (node (ref "GND_T12") (pin "1") (pinfunction "1_1") (pintype "passive"))
      (node (ref "J5_24V") (pin "1") (pinfunction "1_1") (pintype "passive"))
      (node (ref "Motor_Left") (pin "1") (pinfunction "1_1") (pintype "passive"))
      (node (ref "Motor_Right") (pin "1") (pinfunction "1_1") (pintype "passive"))
      (node (ref "STR_CdDtb0") (pin "1") (pinfunction "1_1") (pintype "passive"))
      (node (ref "STR_CdDtb1") (pin "1") (pinfunction "1_1") (pintype "passive"))
      (node (ref "STR_CdDtc1") (pin "1") (pinfunction "1_1") (pintype "passive"))
      (node (ref "STR_CdDtc2") (pin "1") (pinfunction "1_1") (pintype "passive"))
      (node (ref "STR_CdDtc4") (pin "1") (pinfunction "1_1") (pintype "passive"))
      (node (ref "STgnd12") (pin "2") (pinfunction "2_2") (pintype "passive"))
      (node (ref "STgnd24") (pin "1") (pinfunction "1_1") (pintype "passive"))
      (node (ref "Sensor0") (pin "1") (pinfunction "1_1") (pintype "passive"))
      (node (ref "Sensor1") (pin "1") (pinfunction "1_1") (pintype "passive"))
      (node (ref "Sensor2") (pin "1") (pinfunction "1_1") (pintype "passive"))
      (node (ref "Sensor3") (pin "1") (pinfunction "1_1") (pintype "passive"))
      (node (ref "Sensor4") (pin "1") (pinfunction "1_1") (pintype "passive"))
      (node (ref "TR_5V") (pin "2") (pinfunction "-Vin_2") (pintype "passive"))
    )
    (net (code "77") (name "Net-(BP0-+)") (class "Default")
      (node (ref "BP0") (pin "5") (pinfunction "+_5") (pintype "passive"))
      (node (ref "RsLedBP0") (pin "1") (pinfunction "1_1") (pintype "passive"))
    )
    (net (code "78") (name "Net-(BP0-3-Pad2)") (class "Default")
      (node (ref "BP0") (pin "2") (pinfunction "3_2") (pintype "passive"))
      (node (ref "BP0") (pin "4") (pinfunction "4_4") (pintype "passive"))
      (node (ref "RpuBP0") (pin "1") (pinfunction "1_1") (pintype "passive"))
      (node (ref "RsBP0") (pin "1") (pinfunction "1_1") (pintype "passive"))
    )
    (net (code "79") (name "Net-(BP1-+)") (class "Default")
      (node (ref "BP1") (pin "5") (pinfunction "+_5") (pintype "passive"))
      (node (ref "RsLedBP1") (pin "1") (pinfunction "1_1") (pintype "passive"))
    )
    (net (code "80") (name "Net-(BP1-3-Pad2)") (class "Default")
      (node (ref "BP1") (pin "2") (pinfunction "3_2") (pintype "passive"))
      (node (ref "BP1") (pin "4") (pinfunction "4_4") (pintype "passive"))
      (node (ref "RpuBP1") (pin "1") (pinfunction "1_1") (pintype "passive"))
      (node (ref "RsBP1") (pin "1") (pinfunction "1_1") (pintype "passive"))
    )
    (net (code "81") (name "Net-(BP2-+)") (class "Default")
      (node (ref "BP2") (pin "5") (pinfunction "+_5") (pintype "passive"))
      (node (ref "RsLedBP2") (pin "1") (pinfunction "1_1") (pintype "passive"))
    )
    (net (code "82") (name "Net-(BP2-3-Pad2)") (class "Default")
      (node (ref "BP2") (pin "2") (pinfunction "3_2") (pintype "passive"))
      (node (ref "BP2") (pin "4") (pinfunction "4_4") (pintype "passive"))
      (node (ref "RpuBP2") (pin "1") (pinfunction "1_1") (pintype "passive"))
      (node (ref "RsBP2") (pin "1") (pinfunction "1_1") (pintype "passive"))
    )
    (net (code "83") (name "Net-(BP3-+)") (class "Default")
      (node (ref "BP3") (pin "5") (pinfunction "+_5") (pintype "passive"))
      (node (ref "RsLedBP3") (pin "1") (pinfunction "1_1") (pintype "passive"))
    )
    (net (code "84") (name "Net-(BP3-3-Pad2)") (class "Default")
      (node (ref "BP3") (pin "2") (pinfunction "3_2") (pintype "passive"))
      (node (ref "BP3") (pin "4") (pinfunction "4_4") (pintype "passive"))
      (node (ref "RpuBP3") (pin "1") (pinfunction "1_1") (pintype "passive"))
      (node (ref "RsBP3") (pin "1") (pinfunction "1_1") (pintype "passive"))
    )
    (net (code "85") (name "Net-(D24Psce-A)") (class "Default")
      (node (ref "D24Psce") (pin "1") (pinfunction "A_1") (pintype "passive"))
      (node (ref "R24Psce") (pin "2") (pinfunction "2_2") (pintype "passive"))
    )
    (net (code "86") (name "Net-(D24in-A)") (class "Default")
      (node (ref "D24in") (pin "1") (pinfunction "A_1") (pintype "passive"))
      (node (ref "R24in") (pin "2") (pinfunction "2_2") (pintype "passive"))
    )
    (net (code "87") (name "Net-(Dcde-A)") (class "Default")
      (node (ref "Dcde") (pin "1") (pinfunction "A_1") (pintype "passive"))
      (node (ref "Rcde") (pin "2") (pinfunction "2_2") (pintype "passive"))
    )
    (net (code "88") (name "Net-(Dhok-A)") (class "Default")
      (node (ref "Dhok") (pin "1") (pinfunction "A_1") (pintype "passive"))
      (node (ref "Rhok") (pin "2") (pinfunction "2_2") (pintype "passive"))
    )
    (net (code "89") (name "Net-(Dreverse-K)") (class "Default")
      (node (ref "ARU_in") (pin "1") (pinfunction "1_1") (pintype "passive"))
      (node (ref "Cd24VCDE") (pin "2") (pinfunction "2_2") (pintype "passive"))
      (node (ref "Dreverse") (pin "2") (pinfunction "K_2") (pintype "passive"))
      (node (ref "TR_5V") (pin "1") (pinfunction "+Vin_1") (pintype "passive"))
    )
    (net (code "90") (name "Net-(LED_color-C1)") (class "Default")
      (node (ref "LED_color") (pin "4") (pinfunction "C1_4") (pintype "passive"))
      (node (ref "RGreen") (pin "2") (pinfunction "2_2") (pintype "passive"))
    )
    (net (code "91") (name "Net-(LED_color-C2)") (class "Default")
      (node (ref "LED_color") (pin "3") (pinfunction "C2_3") (pintype "passive"))
      (node (ref "Rred") (pin "2") (pinfunction "2_2") (pintype "passive"))
    )
    (net (code "92") (name "Net-(LED_color-C3)") (class "Default")
      (node (ref "LED_color") (pin "2") (pinfunction "C3_2") (pintype "passive"))
      (node (ref "RBlue") (pin "2") (pinfunction "2_2") (pintype "passive"))
    )
    (net (code "93") (name "Net-(Led0-A)") (class "Default")
      (node (ref "Led0") (pin "1") (pinfunction "A_1") (pintype "passive"))
      (node (ref "Rled0") (pin "1") (pinfunction "1_1") (pintype "passive"))
    )
    (net (code "94") (name "Net-(Led1-A)") (class "Default")
      (node (ref "Led1") (pin "1") (pinfunction "A_1") (pintype "passive"))
      (node (ref "Rled1") (pin "1") (pinfunction "1_1") (pintype "passive"))
    )
    (net (code "95") (name "Net-(PRO_RCodDA-Pad2)") (class "Default")
      (node (ref "PRO_RCodDA") (pin "2") (pinfunction "2_2") (pintype "passive"))
      (node (ref "PRO_codDroite") (pin "4") (pinfunction "4_4") (pintype "passive"))
    )
    (net (code "96") (name "Net-(PRO_RCodDB-Pad2)") (class "Default")
      (node (ref "PRO_RCodDB") (pin "2") (pinfunction "2_2") (pintype "passive"))
      (node (ref "PRO_codDroite") (pin "3") (pinfunction "3_3") (pintype "passive"))
    )
    (net (code "97") (name "Net-(PRO_RCodGA-Pad2)") (class "Default")
      (node (ref "PRO_RCodGA") (pin "2") (pinfunction "2_2") (pintype "passive"))
      (node (ref "PRO_codGauche") (pin "4") (pinfunction "4_4") (pintype "passive"))
    )
    (net (code "98") (name "Net-(PRO_RCodGB-Pad2)") (class "Default")
      (node (ref "PRO_RCodGB") (pin "2") (pinfunction "2_2") (pintype "passive"))
      (node (ref "PRO_codGauche") (pin "3") (pinfunction "3_3") (pintype "passive"))
    )
    (net (code "99") (name "Net-(RUS0+-Pad2)") (class "Default")
      (node (ref "RUS0+") (pin "2") (pinfunction "2_2") (pintype "passive"))
      (node (ref "US0") (pin "2") (pinfunction "2_2") (pintype "passive"))
    )
    (net (code "100") (name "Net-(RUS1+-Pad2)") (class "Default")
      (node (ref "RUS1+") (pin "2") (pinfunction "2_2") (pintype "passive"))
      (node (ref "US1") (pin "2") (pinfunction "2_2") (pintype "passive"))
    )
    (net (code "101") (name "Net-(RUS2+-Pad2)") (class "Default")
      (node (ref "RUS2+") (pin "2") (pinfunction "2_2") (pintype "passive"))
      (node (ref "US2") (pin "2") (pinfunction "2_2") (pintype "passive"))
    )
    (net (code "102") (name "Net-(RUS3+-Pad2)") (class "Default")
      (node (ref "RUS3+") (pin "2") (pinfunction "2_2") (pintype "passive"))
      (node (ref "US3") (pin "2") (pinfunction "2_2") (pintype "passive"))
    )
    (net (code "103") (name "Net-(RledBir-Pad1)") (class "Default")
      (node (ref "RledBir") (pin "1") (pinfunction "1_1") (pintype "passive"))
      (node (ref "birouteLed") (pin "1") (pinfunction "1_1") (pintype "passive"))
    )
    (net (code "104") (name "Net-(RpuBir-Pad1)") (class "Default")
      (node (ref "RpuBir") (pin "1") (pinfunction "1_1") (pintype "passive"))
      (node (ref "RsBir") (pin "1") (pinfunction "1_1") (pintype "passive"))
      (node (ref "biroute") (pin "1") (pinfunction "1_1") (pintype "passive"))
    )
    (net (code "105") (name "Net-(RpuSW0-Pad1)") (class "Default")
      (node (ref "RpuSW0") (pin "1") (pinfunction "1_1") (pintype "passive"))
      (node (ref "RsSW0") (pin "1") (pinfunction "1_1") (pintype "passive"))
      (node (ref "SW0") (pin "NC1") (pinfunction "NC1_NC1") (pintype "passive"))
    )
    (net (code "106") (name "Net-(RpuSW1-Pad1)") (class "Default")
      (node (ref "RpuSW1") (pin "1") (pinfunction "1_1") (pintype "passive"))
      (node (ref "RsSW1") (pin "1") (pinfunction "1_1") (pintype "passive"))
      (node (ref "SW1") (pin "NC1") (pinfunction "NC1_NC1") (pintype "passive"))
    )
    (net (code "107") (name "Net-(RpuSW2-Pad1)") (class "Default")
      (node (ref "RpuSW2") (pin "1") (pinfunction "1_1") (pintype "passive"))
      (node (ref "RsSW2") (pin "1") (pinfunction "1_1") (pintype "passive"))
      (node (ref "SW2") (pin "NC1") (pinfunction "NC1_NC1") (pintype "passive"))
    )
    (net (code "108") (name "Net-(RpuSW10-Pad1)") (class "Default")
      (node (ref "RpuSW10") (pin "1") (pinfunction "1_1") (pintype "passive"))
      (node (ref "RsSW10") (pin "1") (pinfunction "1_1") (pintype "passive"))
      (node (ref "SW10") (pin "NC1") (pinfunction "NC1_NC1") (pintype "passive"))
    )
    (net (code "109") (name "Net-(RpuSW11-Pad1)") (class "Default")
      (node (ref "RpuSW11") (pin "1") (pinfunction "1_1") (pintype "passive"))
      (node (ref "RsSW11") (pin "1") (pinfunction "1_1") (pintype "passive"))
      (node (ref "SW11") (pin "NC1") (pinfunction "NC1_NC1") (pintype "passive"))
    )
    (net (code "110") (name "Net-(RpuSW12-Pad1)") (class "Default")
      (node (ref "RpuSW12") (pin "1") (pinfunction "1_1") (pintype "passive"))
      (node (ref "RsSW12") (pin "1") (pinfunction "1_1") (pintype "passive"))
      (node (ref "SW12") (pin "NC1") (pinfunction "NC1_NC1") (pintype "passive"))
    )
    (net (code "111") (name "Net-(STR_Rdtb0-Pad2)") (class "Default")
      (node (ref "STR_Rdtb0") (pin "2") (pinfunction "2_2") (pintype "passive"))
      (node (ref "STR_RfDTb0") (pin "1") (pinfunction "1_1") (pintype "passive"))
      (node (ref "Sensor0") (pin "2") (pinfunction "2_2") (pintype "passive"))
    )
    (net (code "112") (name "Net-(STR_Rdtb1-Pad2)") (class "Default")
      (node (ref "STR_Rdtb1") (pin "2") (pinfunction "2_2") (pintype "passive"))
      (node (ref "STR_RfDTb1") (pin "1") (pinfunction "1_1") (pintype "passive"))
      (node (ref "Sensor1") (pin "2") (pinfunction "2_2") (pintype "passive"))
    )
    (net (code "113") (name "Net-(STR_Rdtc1-Pad2)") (class "Default")
      (node (ref "STR_Rdtc1") (pin "2") (pinfunction "2_2") (pintype "passive"))
      (node (ref "STR_RfDTc1") (pin "1") (pinfunction "1_1") (pintype "passive"))
      (node (ref "Sensor2") (pin "2") (pinfunction "2_2") (pintype "passive"))
    )
    (net (code "114") (name "Net-(STR_Rdtc2-Pad2)") (class "Default")
      (node (ref "STR_Rdtc2") (pin "2") (pinfunction "2_2") (pintype "passive"))
      (node (ref "STR_RfDTc2") (pin "1") (pinfunction "1_1") (pintype "passive"))
      (node (ref "Sensor3") (pin "2") (pinfunction "2_2") (pintype "passive"))
    )
    (net (code "115") (name "Net-(STR_Rdtc4-Pad2)") (class "Default")
      (node (ref "STR_Rdtc4") (pin "2") (pinfunction "2_2") (pintype "passive"))
      (node (ref "STR_RfDTc4") (pin "1") (pinfunction "1_1") (pintype "passive"))
      (node (ref "Sensor4") (pin "2") (pinfunction "2_2") (pintype "passive"))
    )
    (net (code "116") (name "unconnected-(STR_STM32F4DISCOVERY-BOOT0{slash}VPP-Pad71)") (class "Default")
      (node (ref "STR_STM32F4DISCOVERY") (pin "71") (pinfunction "BOOT0/VPP_71") (pintype "passive"))
    )
    (net (code "117") (name "unconnected-(STR_STM32F4DISCOVERY-NC-Pad48)") (class "Default")
      (node (ref "STR_STM32F4DISCOVERY") (pin "48") (pinfunction "NC_48") (pintype "passive+no_connect"))
    )
    (net (code "118") (name "unconnected-(STR_STM32F4DISCOVERY-NRST-Pad6)") (class "Default")
      (node (ref "STR_STM32F4DISCOVERY") (pin "6") (pinfunction "NRST_6") (pintype "passive+no_connect"))
    )
    (net (code "119") (name "unconnected-(STR_STM32F4DISCOVERY-PA4{slash}SPI1_NSS{slash}SPI3_NSS{slash}USART2_CK{slash}DCMI_HSYNC{slash}OTG_HS_SOF{slash}I2S3_WS{slash}ADC12_IN4{slash}DAC1_OUT-Pad16)") (class "Default")
      (node (ref "STR_STM32F4DISCOVERY") (pin "16") (pinfunction "PA4/SPI1_NSS/SPI3_NSS/USART2_CK/DCMI_HSYNC/OTG_HS_SOF/I2S3_WS/ADC12_IN4/DAC1_OUT_16") (pintype "passive+no_connect"))
    )
    (net (code "120") (name "unconnected-(STR_STM32F4DISCOVERY-PA6{slash}SPI1_MISO{slash}TIM8_BKIN{slash}TIM13_CH1{slash}DCMI_PIXCLK{slash}TIM3_CH1{slash}TIM1_BKIN{slash}ADC12_IN6-Pad18)") (class "Default")
      (node (ref "STR_STM32F4DISCOVERY") (pin "18") (pinfunction "PA6/SPI1_MISO/TIM8_BKIN/TIM13_CH1/DCMI_PIXCLK/TIM3_CH1/TIM1_BKIN/ADC12_IN6_18") (pintype "passive"))
    )
    (net (code "121") (name "unconnected-(STR_STM32F4DISCOVERY-PA7{slash}SPI1_MOSI{slash}TIM8_CH1N{slash}TIM14_CH1TIM3_CH2{slash}ETH_MII_RX_DV{slash}TIM1_CH1N{slash}RMII_CRS_DV{slash}ADC12_IN7-Pad17)") (class "Default")
      (node (ref "STR_STM32F4DISCOVERY") (pin "17") (pinfunction "PA7/SPI1_MOSI/TIM8_CH1N/TIM14_CH1TIM3_CH2/ETH_MII_RX_DV/TIM1_CH1N/RMII_CRS_DV/ADC12_IN7_17") (pintype "passive"))
    )
    (net (code "122") (name "unconnected-(STR_STM32F4DISCOVERY-PA9{slash}USART1_TX{slash}TIM1_CH2{slash}I2C3_SMBA{slash}DCMI_D0{slash}OTG_FS_VBUS-Pad94)") (class "Default")
      (node (ref "STR_STM32F4DISCOVERY") (pin "94") (pinfunction "PA9/USART1_TX/TIM1_CH2/I2C3_SMBA/DCMI_D0/OTG_FS_VBUS_94") (pintype "passive"))
    )
    (net (code "123") (name "unconnected-(STR_STM32F4DISCOVERY-PA10{slash}USART1_RX{slash}TIM1_CH3{slash}OTG_FS_ID{slash}DCMI_D1-Pad91)") (class "Default")
      (node (ref "STR_STM32F4DISCOVERY") (pin "91") (pinfunction "PA10/USART1_RX/TIM1_CH3/OTG_FS_ID/DCMI_D1_91") (pintype "passive"))
    )
    (net (code "124") (name "unconnected-(STR_STM32F4DISCOVERY-PA13{slash}JTMS_SWDIO-Pad92)") (class "Default")
      (node (ref "STR_STM32F4DISCOVERY") (pin "92") (pinfunction "PA13/JTMS_SWDIO_92") (pintype "passive"))
    )
    (net (code "125") (name "unconnected-(STR_STM32F4DISCOVERY-PA14{slash}JTCK_SWCLK-Pad89)") (class "Default")
      (node (ref "STR_STM32F4DISCOVERY") (pin "89") (pinfunction "PA14/JTCK_SWCLK_89") (pintype "passive"))
    )
    (net (code "126") (name "unconnected-(STR_STM32F4DISCOVERY-PB3{slash}JTDO{slash}TRACESWO{slash}SPI3_SCK{slash}I2S3_CK{slash}TIM2_CH2{slash}SPI1_SCK-Pad78)") (class "Default")
      (node (ref "STR_STM32F4DISCOVERY") (pin "78") (pinfunction "PB3/JTDO/TRACESWO/SPI3_SCK/I2S3_CK/TIM2_CH2/SPI1_SCK_78") (pintype "passive+no_connect"))
    )
    (net (code "127") (name "unconnected-(STR_STM32F4DISCOVERY-PC0{slash}OTG_HS_ULPI_STP{slash}ADC123_IN10-Pad8)") (class "Default")
      (node (ref "STR_STM32F4DISCOVERY") (pin "8") (pinfunction "PC0/OTG_HS_ULPI_STP/ADC123_IN10_8") (pintype "passive+no_connect"))
    )
    (net (code "128") (name "unconnected-(STR_STM32F4DISCOVERY-PC3{slash}SPI2_MOSI{slash}I2S2_SD{slash}OTG_HS_ULPI_NXT{slash}ETH_MII_TX_CLK{slash}ADC123_IN13-Pad9)") (class "Default")
      (node (ref "STR_STM32F4DISCOVERY") (pin "9") (pinfunction "PC3/SPI2_MOSI/I2S2_SD/OTG_HS_ULPI_NXT/ETH_MII_TX_CLK/ADC123_IN13_9") (pintype "passive"))
    )
    (net (code "129") (name "unconnected-(STR_STM32F4DISCOVERY-PC5{slash}ETH_RMII_RX_D1{slash}ETH_MII_RX_D1{slash}ADC12_IN15-Pad19)") (class "Default")
      (node (ref "STR_STM32F4DISCOVERY") (pin "19") (pinfunction "PC5/ETH_RMII_RX_D1/ETH_MII_RX_D1/ADC12_IN15_19") (pintype "passive"))
    )
    (net (code "130") (name "unconnected-(STR_STM32F4DISCOVERY-PC13{slash}RTC_AF1-Pad62)") (class "Default")
      (node (ref "STR_STM32F4DISCOVERY") (pin "62") (pinfunction "PC13/RTC_AF1_62") (pintype "passive"))
    )
    (net (code "131") (name "unconnected-(STR_STM32F4DISCOVERY-PC14{slash}OSC32_IN-Pad59)") (class "Default")
      (node (ref "STR_STM32F4DISCOVERY") (pin "59") (pinfunction "PC14/OSC32_IN_59") (pintype "passive"))
    )
    (net (code "132") (name "unconnected-(STR_STM32F4DISCOVERY-PC15{slash}OSC32_OUT-Pad60)") (class "Default")
      (node (ref "STR_STM32F4DISCOVERY") (pin "60") (pinfunction "PC15/OSC32_OUT_60") (pintype "passive"))
    )
    (net (code "133") (name "unconnected-(STR_STM32F4DISCOVERY-PD4{slash}FSMC_NOE{slash}USART2_RTS-Pad82)") (class "Default")
      (node (ref "STR_STM32F4DISCOVERY") (pin "82") (pinfunction "PD4/FSMC_NOE/USART2_RTS_82") (pintype "passive"))
    )
    (net (code "134") (name "unconnected-(STR_STM32F4DISCOVERY-PD5{slash}FSMC_NWE{slash}USART2_TX-Pad79)") (class "Default")
      (node (ref "STR_STM32F4DISCOVERY") (pin "79") (pinfunction "PD5/FSMC_NWE/USART2_TX_79") (pintype "passive"))
    )
    (net (code "135") (name "unconnected-(STR_STM32F4DISCOVERY-PE2{slash}TRACECLK{slash}FSMC_A23{slash}ETH_MII_TXD3-Pad65)") (class "Default")
      (node (ref "STR_STM32F4DISCOVERY") (pin "65") (pinfunction "PE2/TRACECLK/FSMC_A23/ETH_MII_TXD3_65") (pintype "passive"))
    )
    (net (code "136") (name "unconnected-(STR_STM32F4DISCOVERY-PE11{slash}FSMC_D8{slash}TIM1_CH2-Pad29)") (class "Default")
      (node (ref "STR_STM32F4DISCOVERY") (pin "29") (pinfunction "PE11/FSMC_D8/TIM1_CH2_29") (pintype "passive"))
    )
    (net (code "137") (name "unconnected-(STR_STM32F4DISCOVERY-PH0{slash}OSC_IN-Pad57)") (class "Default")
      (node (ref "STR_STM32F4DISCOVERY") (pin "57") (pinfunction "PH0/OSC_IN_57") (pintype "passive+no_connect"))
    )
    (net (code "138") (name "unconnected-(STR_STM32F4DISCOVERY-PH1{slash}OSC_OUT-Pad58)") (class "Default")
      (node (ref "STR_STM32F4DISCOVERY") (pin "58") (pinfunction "PH1/OSC_OUT_58") (pintype "passive"))
    )
    (net (code "139") (name "unconnected-(STR_STM32F4DISCOVERY-VDD-Pad3)") (class "Default")
      (node (ref "STR_STM32F4DISCOVERY") (pin "3") (pinfunction "VDD_3") (pintype "passive+no_connect"))
    )
    (net (code "140") (name "unconnected-(STR_STM32F4DISCOVERY-VDD-Pad4)") (class "Default")
      (node (ref "STR_STM32F4DISCOVERY") (pin "4") (pinfunction "VDD_4") (pintype "passive+no_connect"))
    )
    (net (code "141") (name "unconnected-(STR_STM32F4DISCOVERY-VDD-Pad72)") (class "Default")
      (node (ref "STR_STM32F4DISCOVERY") (pin "72") (pinfunction "VDD_72") (pintype "passive"))
    )
    (net (code "142") (name "unconnected-(STR_Ucan-VREF-Pad5)") (class "Default")
      (node (ref "STR_Ucan") (pin "5") (pinfunction "VREF_5") (pintype "output"))
    )
    (net (code "143") (name "unconnected-(SW0-PadNO1)") (class "Default")
      (node (ref "SW0") (pin "NO1") (pinfunction "NO1_NO1") (pintype "passive+no_connect"))
    )
    (net (code "144") (name "unconnected-(SW1-PadNO1)") (class "Default")
      (node (ref "SW1") (pin "NO1") (pinfunction "NO1_NO1") (pintype "passive+no_connect"))
    )
    (net (code "145") (name "unconnected-(SW2-PadNO1)") (class "Default")
      (node (ref "SW2") (pin "NO1") (pinfunction "NO1_NO1") (pintype "passive+no_connect"))
    )
    (net (code "146") (name "unconnected-(SW10-PadNO1)") (class "Default")
      (node (ref "SW10") (pin "NO1") (pinfunction "NO1_NO1") (pintype "passive+no_connect"))
    )
    (net (code "147") (name "unconnected-(SW11-PadNO1)") (class "Default")
      (node (ref "SW11") (pin "NO1") (pinfunction "NO1_NO1") (pintype "passive+no_connect"))
    )
    (net (code "148") (name "unconnected-(SW12-PadNO1)") (class "Default")
      (node (ref "SW12") (pin "NO1") (pinfunction "NO1_NO1") (pintype "passive+no_connect"))
    )
    (net (code "149") (name "unconnected-(TR_5V-on_off-Pad6)") (class "Default")
      (node (ref "TR_5V") (pin "6") (pinfunction "on_off_6") (pintype "passive+no_connect"))
    )
    (net (code "150") (name "unconnected-(TR_5V-trim-Pad4)") (class "Default")
      (node (ref "TR_5V") (pin "4") (pinfunction "trim_4") (pintype "passive+no_connect"))
    )
  )
)
